# 03_-_28Pins_Schematic.net
KiCad netlist of a schematic drawn in Altium Designer
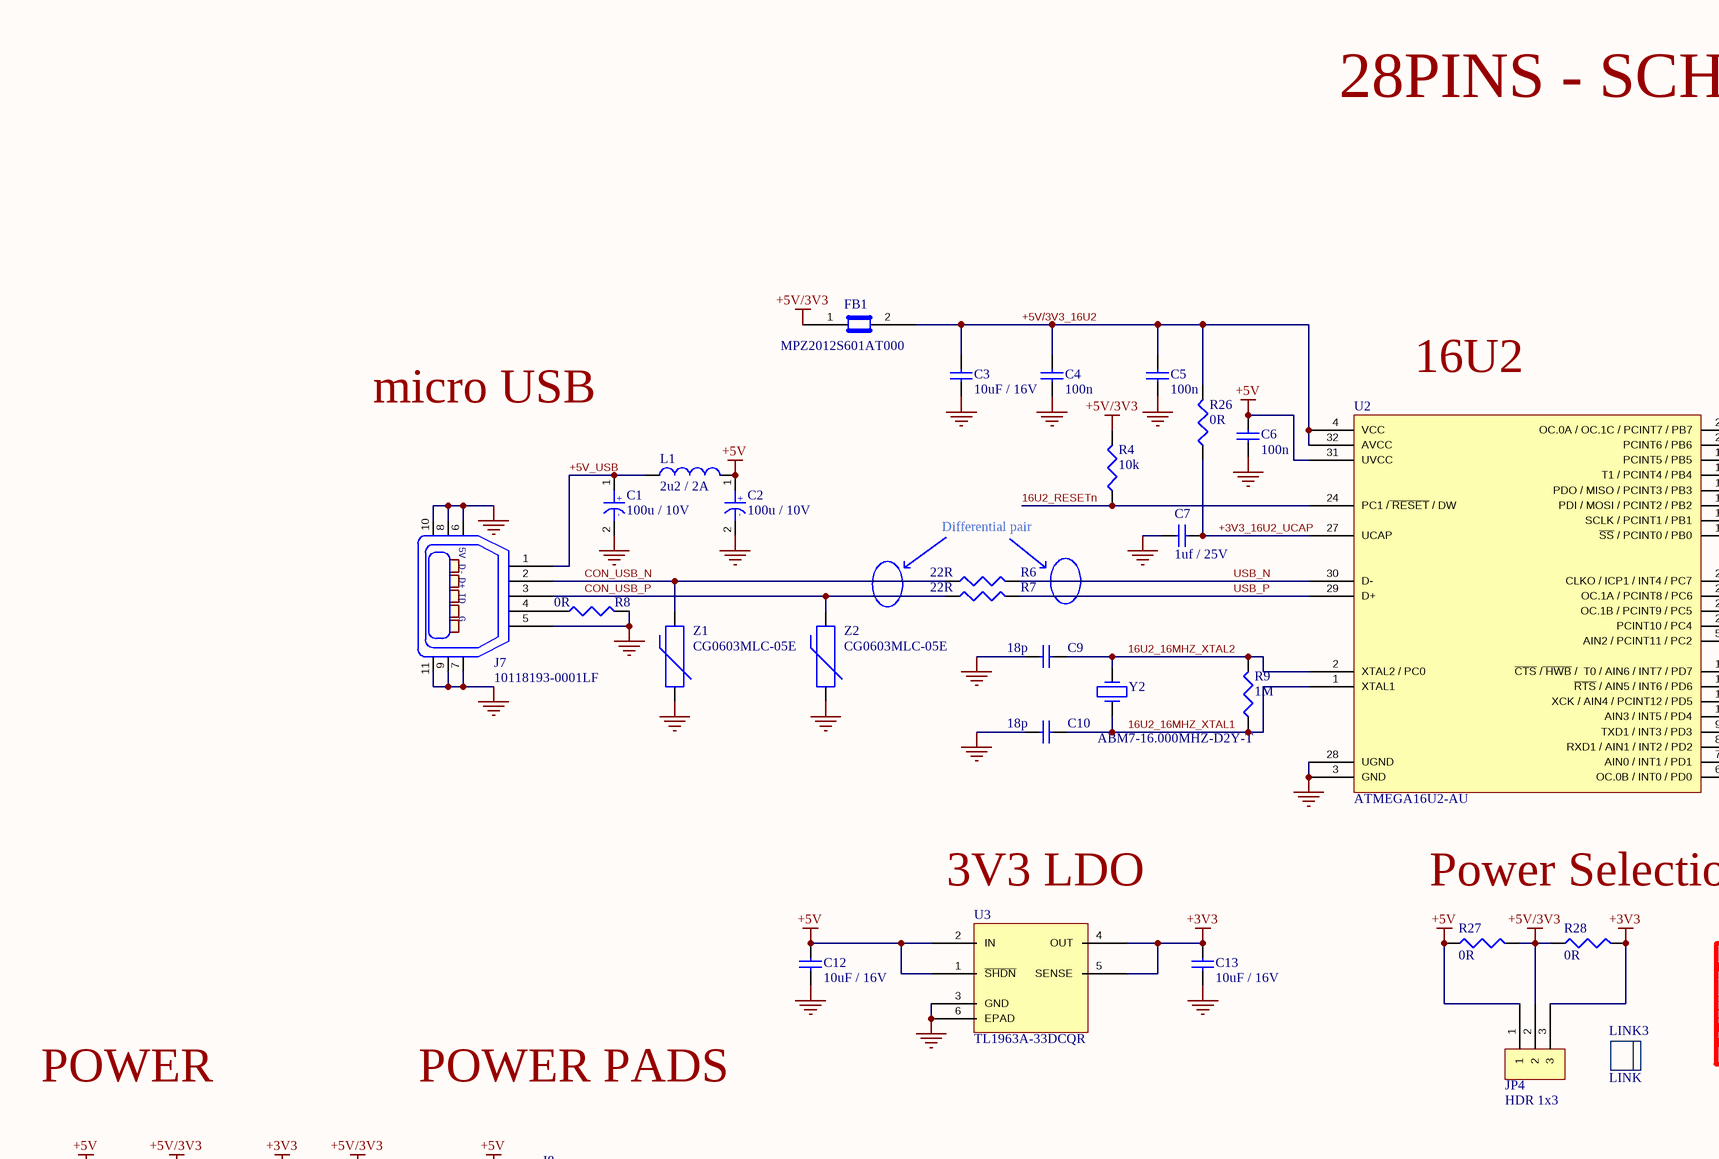
[diagram p0: [03] - 28Pins_Schematic.SchDoc, top left]
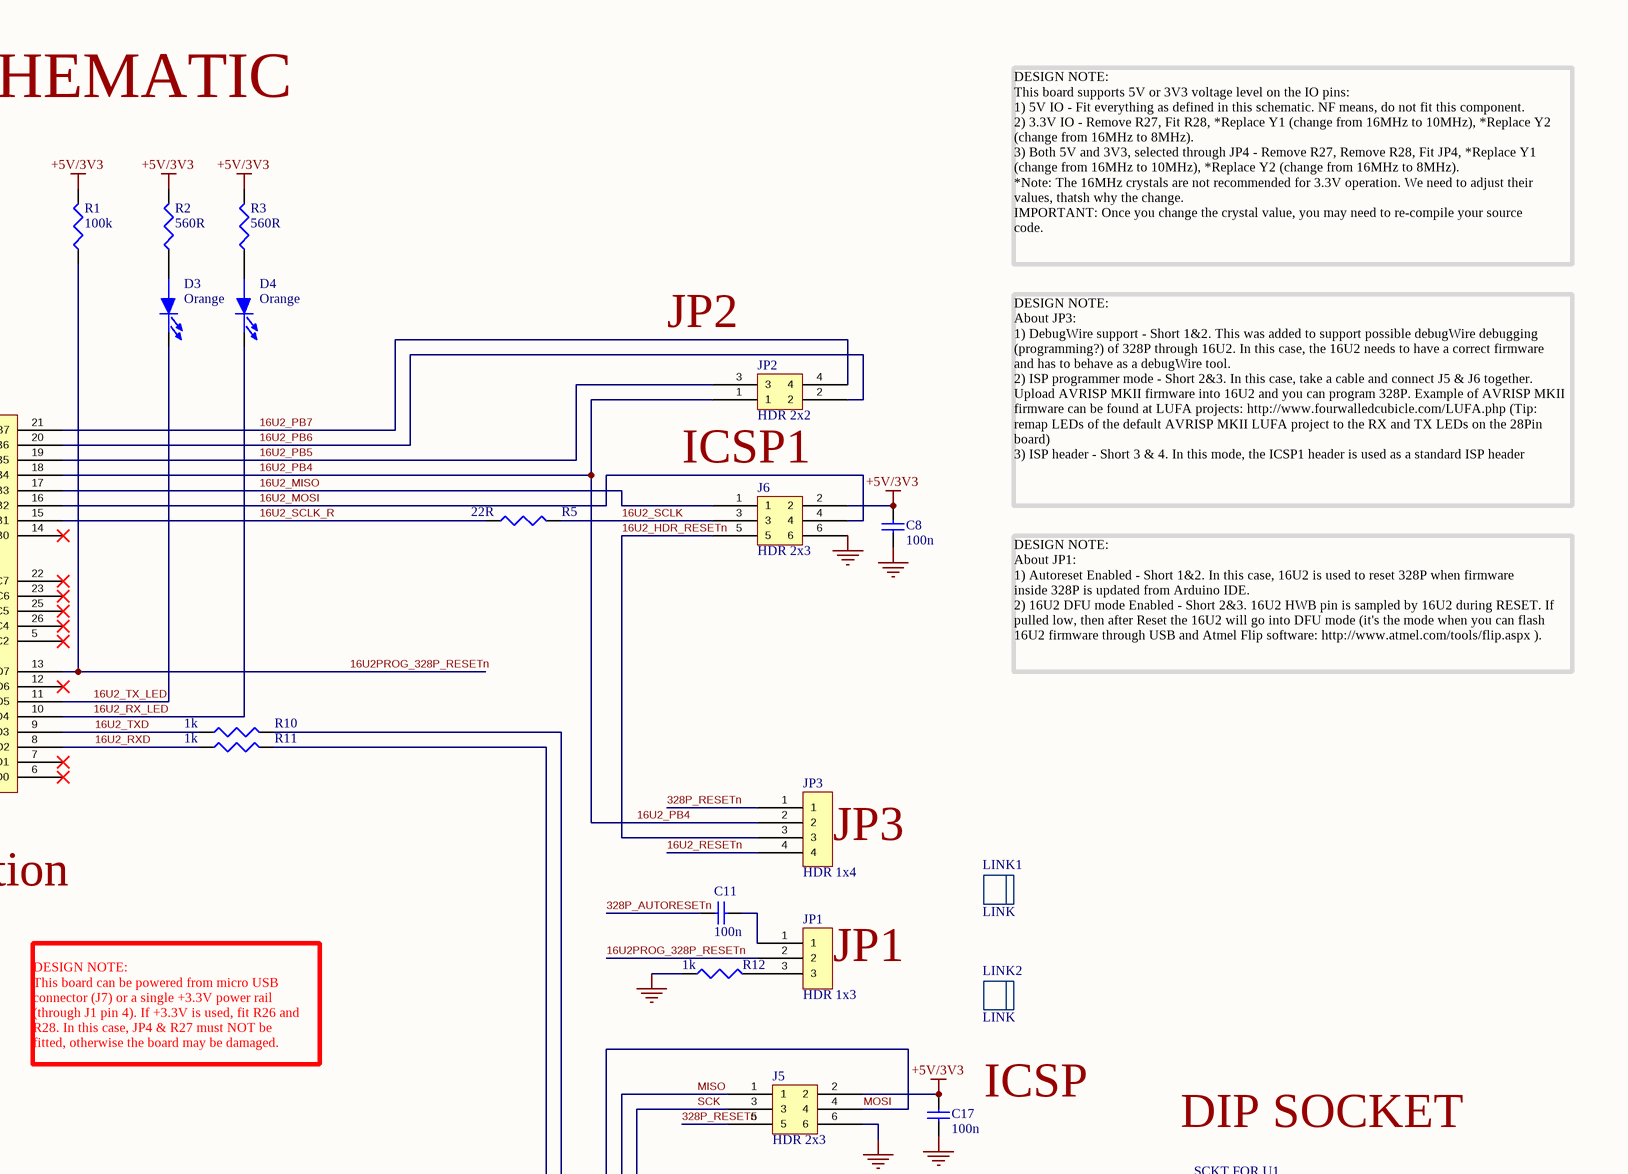
[diagram p1: [03] - 28Pins_Schematic.SchDoc, top right]
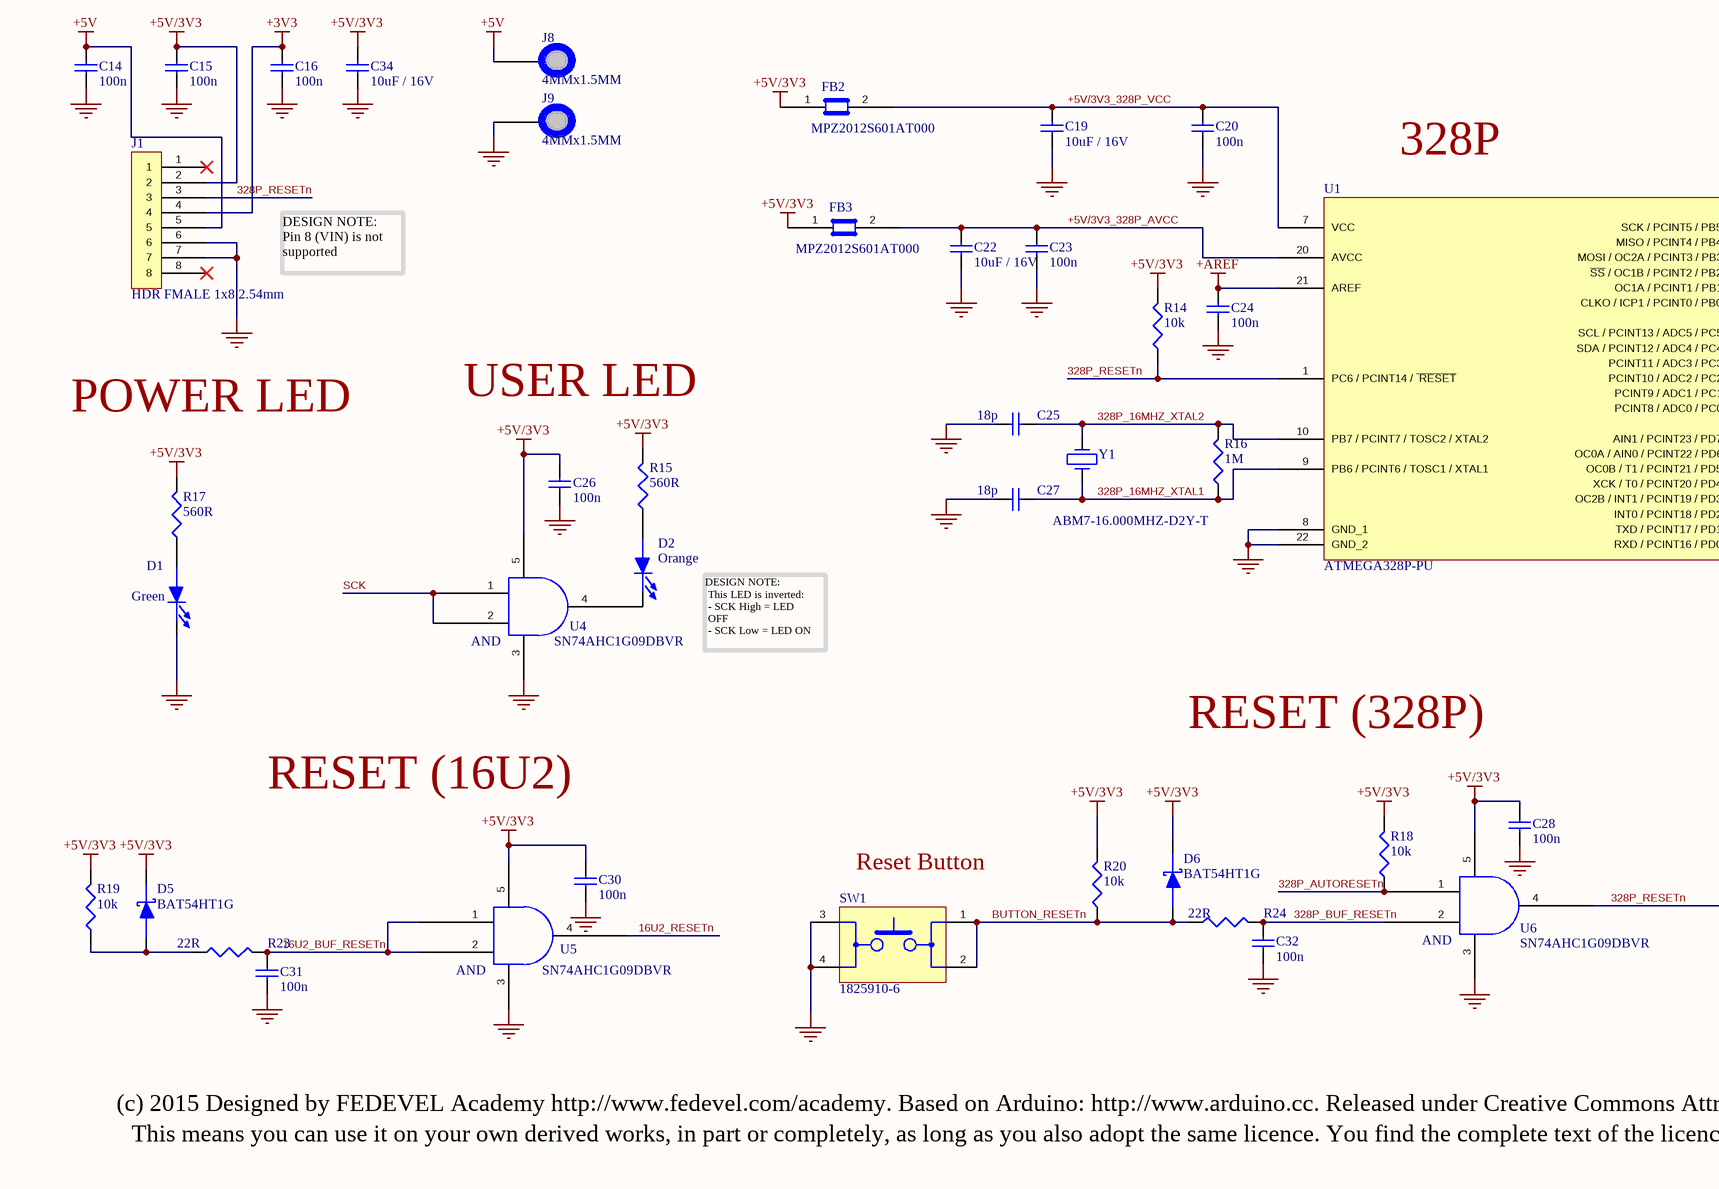
[diagram p2: [03] - 28Pins_Schematic.SchDoc, bottom left]
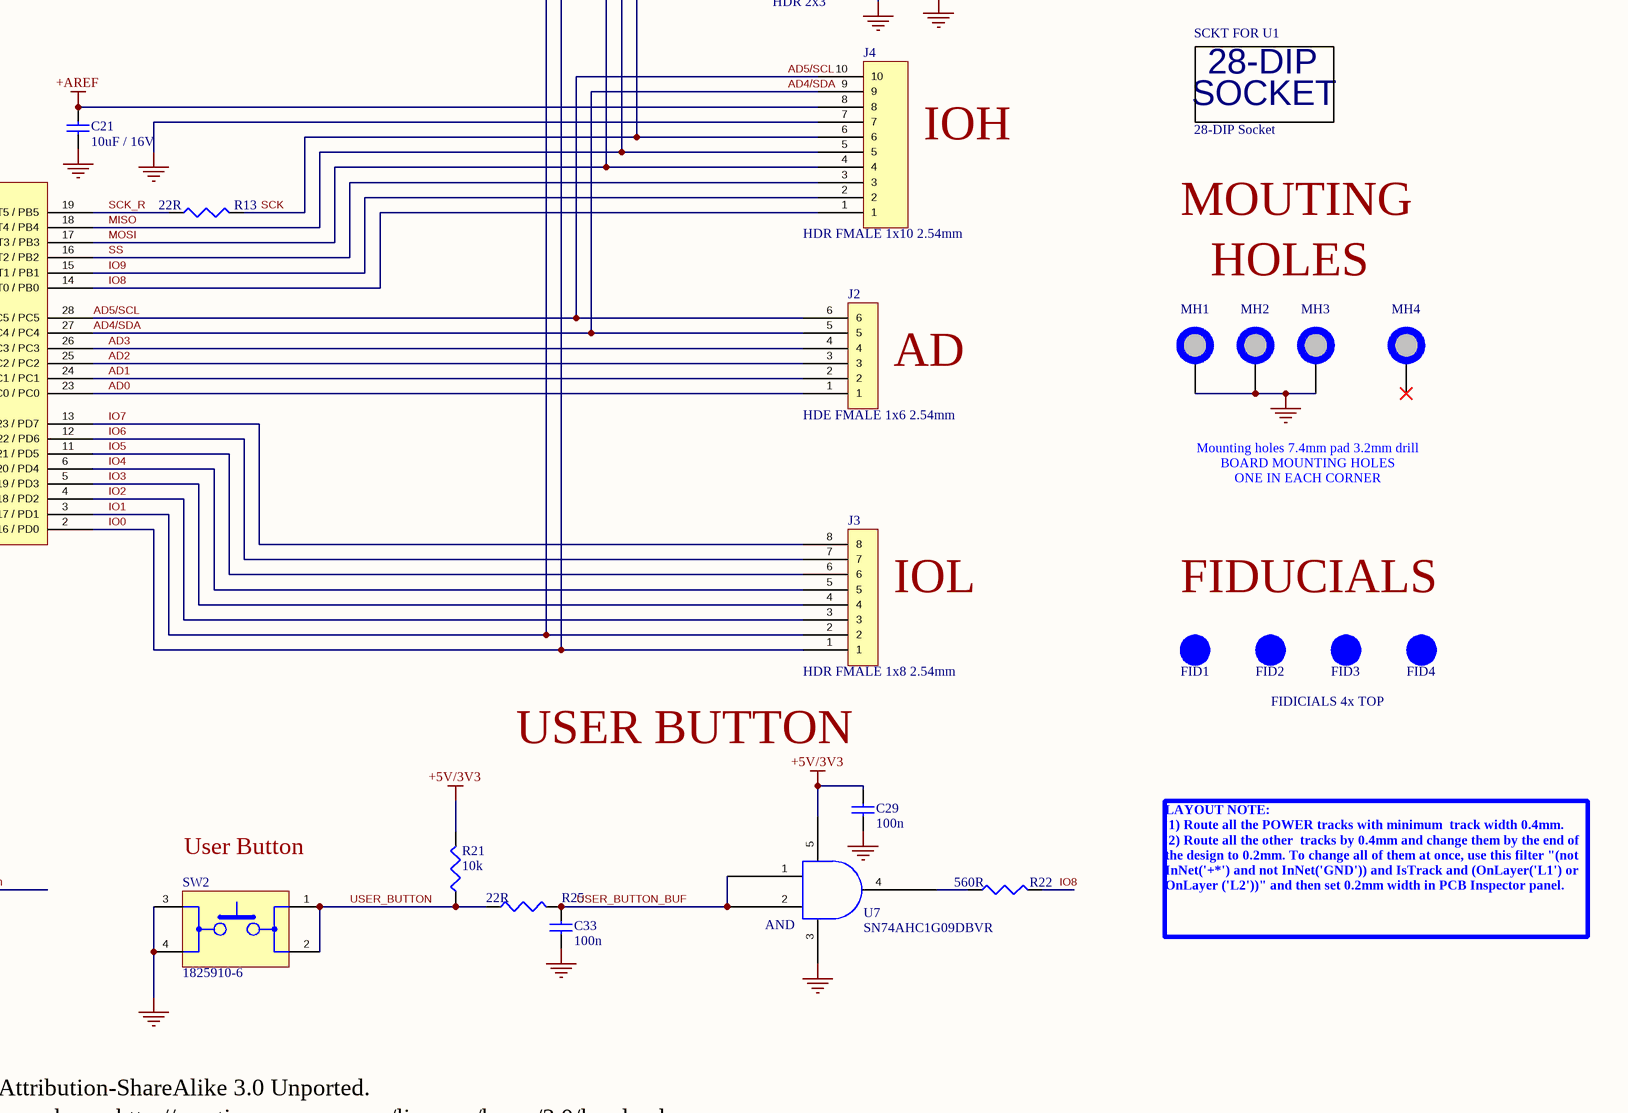
[diagram p3: [03] - 28Pins_Schematic.SchDoc, bottom right]

(export (version "E")
  (design (tool "Eeschema 10.0.6"))
  (components
    (comp (ref "C1")
      (value "100u / 10V")
      (footprint "C_ALU_C_SIZE")
      (description "Cap Aluminum Lytic 100uF 10V 20% (5 X 5.4mm) SMD 50mA 1000h 85C Automotive T/R")
      (fields
        (field (name "MANUFACTURER") "Panasonic")
        (field (name "MANUFACTURER PART NUMBER") "EEE-1AA101WR")
      )
      (libsource (lib "28Pins_Project_V1I1") (part "EEE-1AA101WR"))
    )
    (comp (ref "C2")
      (value "100u / 10V")
      (footprint "C_ALU_C_SIZE")
      (description "Cap Aluminum Lytic 100uF 10V 20% (5 X 5.4mm) SMD 50mA 1000h 85C Automotive T/R")
      (fields
        (field (name "MANUFACTURER") "Panasonic")
        (field (name "MANUFACTURER PART NUMBER") "EEE-1AA101WR")
      )
      (libsource (lib "28Pins_Project_V1I1") (part "EEE-1AA101WR"))
    )
    (comp (ref "C3")
      (value "10uF / 16V")
      (footprint "C0805 - 10uf")
      (description "CAP CER 10UF 16V X5R 0805")
      (fields
        (field (name "MANUFACTURER") "TDK")
        (field (name "MANUFACTURER PART NUMBER") "C2012X5R1C106M125AC")
      )
      (libsource (lib "28Pins_Project_V1I1") (part "C2012X5R1C106M125AC"))
    )
    (comp (ref "C4")
      (value "100n")
      (footprint "C0805")
      (description "CAP CER 0.1UF 50V X7R 0805")
      (fields
        (field (name "MANUFACTURER") "TDK")
        (field (name "MANUFACTURER PART NUMBER") "C2012X7R1H104K085AA")
      )
      (libsource (lib "28Pins_Project_V1I1") (part "C2012X7R1H104K085AA"))
    )
    (comp (ref "C5")
      (value "100n")
      (footprint "C0805")
      (description "CAP CER 0.1UF 50V X7R 0805")
      (fields
        (field (name "MANUFACTURER") "TDK")
        (field (name "MANUFACTURER PART NUMBER") "C2012X7R1H104K085AA")
      )
      (libsource (lib "28Pins_Project_V1I1") (part "C2012X7R1H104K085AA"))
    )
    (comp (ref "C6")
      (value "100n")
      (footprint "C0805")
      (description "CAP CER 0.1UF 50V X7R 0805")
      (fields
        (field (name "MANUFACTURER") "TDK")
        (field (name "MANUFACTURER PART NUMBER") "C2012X7R1H104K085AA")
      )
      (libsource (lib "28Pins_Project_V1I1") (part "C2012X7R1H104K085AA"))
    )
    (comp (ref "C7")
      (value "1uf / 25V")
      (footprint "C0805")
      (description "CAP CER 1UF 25V X5R 0805")
      (fields
        (field (name "MANUFACTURER") "TDK")
        (field (name "MANUFACTURER PART NUMBER") "C2012X5R1E105K125AA")
      )
      (libsource (lib "28Pins_Project_V1I1") (part "C2012X5R1E105K125AA"))
    )
    (comp (ref "C8")
      (value "100n")
      (footprint "C0805")
      (description "CAP CER 0.1UF 50V X7R 0805")
      (fields
        (field (name "MANUFACTURER") "TDK")
        (field (name "MANUFACTURER PART NUMBER") "C2012X7R1H104K085AA")
      )
      (libsource (lib "28Pins_Project_V1I1") (part "C2012X7R1H104K085AA"))
    )
    (comp (ref "C9")
      (value "18p")
      (footprint "C0805")
      (description "CAP CER 18PF 50V NP0 0805")
      (fields
        (field (name "MANUFACTURER") "KEMET")
        (field (name "MANUFACTURER PART NUMBER") "C0805C180J5GAC-TU")
      )
      (libsource (lib "28Pins_Project_V1I1") (part "C0805C180J5GAC-TU"))
    )
    (comp (ref "C10")
      (value "18p")
      (footprint "C0805")
      (description "CAP CER 18PF 50V NP0 0805")
      (fields
        (field (name "MANUFACTURER") "KEMET")
        (field (name "MANUFACTURER PART NUMBER") "C0805C180J5GAC-TU")
      )
      (libsource (lib "28Pins_Project_V1I1") (part "C0805C180J5GAC-TU"))
    )
    (comp (ref "C11")
      (value "100n")
      (footprint "C0805")
      (description "CAP CER 0.1UF 50V X7R 0805")
      (fields
        (field (name "MANUFACTURER") "TDK")
        (field (name "MANUFACTURER PART NUMBER") "C2012X7R1H104K085AA")
      )
      (libsource (lib "28Pins_Project_V1I1") (part "C2012X7R1H104K085AA"))
    )
    (comp (ref "C12")
      (value "10uF / 16V")
      (footprint "C0805 - 10uf")
      (description "CAP CER 10UF 16V X5R 0805")
      (fields
        (field (name "MANUFACTURER") "TDK")
        (field (name "MANUFACTURER PART NUMBER") "C2012X5R1C106M125AC")
      )
      (libsource (lib "28Pins_Project_V1I1") (part "C2012X5R1C106M125AC"))
    )
    (comp (ref "C13")
      (value "10uF / 16V")
      (footprint "C0805 - 10uf")
      (description "CAP CER 10UF 16V X5R 0805")
      (fields
        (field (name "MANUFACTURER") "TDK")
        (field (name "MANUFACTURER PART NUMBER") "C2012X5R1C106M125AC")
      )
      (libsource (lib "28Pins_Project_V1I1") (part "C2012X5R1C106M125AC"))
    )
    (comp (ref "C14")
      (value "100n")
      (footprint "C0805")
      (description "CAP CER 0.1UF 50V X7R 0805")
      (fields
        (field (name "MANUFACTURER") "TDK")
        (field (name "MANUFACTURER PART NUMBER") "C2012X7R1H104K085AA")
      )
      (libsource (lib "28Pins_Project_V1I1") (part "C2012X7R1H104K085AA"))
    )
    (comp (ref "C15")
      (value "100n")
      (footprint "C0805")
      (description "CAP CER 0.1UF 50V X7R 0805")
      (fields
        (field (name "MANUFACTURER") "TDK")
        (field (name "MANUFACTURER PART NUMBER") "C2012X7R1H104K085AA")
      )
      (libsource (lib "28Pins_Project_V1I1") (part "C2012X7R1H104K085AA"))
    )
    (comp (ref "C16")
      (value "100n")
      (footprint "C0805")
      (description "CAP CER 0.1UF 50V X7R 0805")
      (fields
        (field (name "MANUFACTURER") "TDK")
        (field (name "MANUFACTURER PART NUMBER") "C2012X7R1H104K085AA")
      )
      (libsource (lib "28Pins_Project_V1I1") (part "C2012X7R1H104K085AA"))
    )
    (comp (ref "C17")
      (value "100n")
      (footprint "C0805")
      (description "CAP CER 0.1UF 50V X7R 0805")
      (fields
        (field (name "MANUFACTURER") "TDK")
        (field (name "MANUFACTURER PART NUMBER") "C2012X7R1H104K085AA")
      )
      (libsource (lib "28Pins_Project_V1I1") (part "C2012X7R1H104K085AA"))
    )
    (comp (ref "C19")
      (value "10uF / 16V")
      (footprint "C0805 - 10uf")
      (description "CAP CER 10UF 16V X5R 0805")
      (fields
        (field (name "MANUFACTURER") "TDK")
        (field (name "MANUFACTURER PART NUMBER") "C2012X5R1C106M125AC")
      )
      (libsource (lib "28Pins_Project_V1I1") (part "C2012X5R1C106M125AC"))
    )
    (comp (ref "C20")
      (value "100n")
      (footprint "C0805")
      (description "CAP CER 0.1UF 50V X7R 0805")
      (fields
        (field (name "MANUFACTURER") "TDK")
        (field (name "MANUFACTURER PART NUMBER") "C2012X7R1H104K085AA")
      )
      (libsource (lib "28Pins_Project_V1I1") (part "C2012X7R1H104K085AA"))
    )
    (comp (ref "C21")
      (value "10uF / 16V")
      (footprint "C0805 - 10uf")
      (description "CAP CER 10UF 16V X5R 0805")
      (fields
        (field (name "MANUFACTURER") "TDK")
        (field (name "MANUFACTURER PART NUMBER") "C2012X5R1C106M125AC")
      )
      (libsource (lib "28Pins_Project_V1I1") (part "C2012X5R1C106M125AC"))
    )
    (comp (ref "C22")
      (value "10uF / 16V")
      (footprint "C0805 - 10uf")
      (description "CAP CER 10UF 16V X5R 0805")
      (fields
        (field (name "MANUFACTURER") "TDK")
        (field (name "MANUFACTURER PART NUMBER") "C2012X5R1C106M125AC")
      )
      (libsource (lib "28Pins_Project_V1I1") (part "C2012X5R1C106M125AC"))
    )
    (comp (ref "C23")
      (value "100n")
      (footprint "C0805")
      (description "CAP CER 0.1UF 50V X7R 0805")
      (fields
        (field (name "MANUFACTURER") "TDK")
        (field (name "MANUFACTURER PART NUMBER") "C2012X7R1H104K085AA")
      )
      (libsource (lib "28Pins_Project_V1I1") (part "C2012X7R1H104K085AA"))
    )
    (comp (ref "C24")
      (value "100n")
      (footprint "C0805")
      (description "CAP CER 0.1UF 50V X7R 0805")
      (fields
        (field (name "MANUFACTURER") "TDK")
        (field (name "MANUFACTURER PART NUMBER") "C2012X7R1H104K085AA")
      )
      (libsource (lib "28Pins_Project_V1I1") (part "C2012X7R1H104K085AA"))
    )
    (comp (ref "C25")
      (value "18p")
      (footprint "C0805")
      (description "CAP CER 18PF 50V NP0 0805")
      (fields
        (field (name "MANUFACTURER") "KEMET")
        (field (name "MANUFACTURER PART NUMBER") "C0805C180J5GAC-TU")
      )
      (libsource (lib "28Pins_Project_V1I1") (part "C0805C180J5GAC-TU"))
    )
    (comp (ref "C26")
      (value "100n")
      (footprint "C0805")
      (description "CAP CER 0.1UF 50V X7R 0805")
      (fields
        (field (name "MANUFACTURER") "TDK")
        (field (name "MANUFACTURER PART NUMBER") "C2012X7R1H104K085AA")
      )
      (libsource (lib "28Pins_Project_V1I1") (part "C2012X7R1H104K085AA"))
    )
    (comp (ref "C27")
      (value "18p")
      (footprint "C0805")
      (description "CAP CER 18PF 50V NP0 0805")
      (fields
        (field (name "MANUFACTURER") "KEMET")
        (field (name "MANUFACTURER PART NUMBER") "C0805C180J5GAC-TU")
      )
      (libsource (lib "28Pins_Project_V1I1") (part "C0805C180J5GAC-TU"))
    )
    (comp (ref "C28")
      (value "100n")
      (footprint "C0805")
      (description "CAP CER 0.1UF 50V X7R 0805")
      (fields
        (field (name "MANUFACTURER") "TDK")
        (field (name "MANUFACTURER PART NUMBER") "C2012X7R1H104K085AA")
      )
      (libsource (lib "28Pins_Project_V1I1") (part "C2012X7R1H104K085AA"))
    )
    (comp (ref "C29")
      (value "100n")
      (footprint "C0805")
      (description "CAP CER 0.1UF 50V X7R 0805")
      (fields
        (field (name "MANUFACTURER") "TDK")
        (field (name "MANUFACTURER PART NUMBER") "C2012X7R1H104K085AA")
      )
      (libsource (lib "28Pins_Project_V1I1") (part "C2012X7R1H104K085AA"))
    )
    (comp (ref "C30")
      (value "100n")
      (footprint "C0805")
      (description "CAP CER 0.1UF 50V X7R 0805")
      (fields
        (field (name "MANUFACTURER") "TDK")
        (field (name "MANUFACTURER PART NUMBER") "C2012X7R1H104K085AA")
      )
      (libsource (lib "28Pins_Project_V1I1") (part "C2012X7R1H104K085AA"))
    )
    (comp (ref "C31")
      (value "100n")
      (footprint "C0805")
      (description "CAP CER 0.1UF 50V X7R 0805")
      (fields
        (field (name "MANUFACTURER") "TDK")
        (field (name "MANUFACTURER PART NUMBER") "C2012X7R1H104K085AA")
      )
      (libsource (lib "28Pins_Project_V1I1") (part "C2012X7R1H104K085AA"))
    )
    (comp (ref "C32")
      (value "100n")
      (footprint "C0805")
      (description "CAP CER 0.1UF 50V X7R 0805")
      (fields
        (field (name "MANUFACTURER") "TDK")
        (field (name "MANUFACTURER PART NUMBER") "C2012X7R1H104K085AA")
      )
      (libsource (lib "28Pins_Project_V1I1") (part "C2012X7R1H104K085AA"))
    )
    (comp (ref "C33")
      (value "100n")
      (footprint "C0805")
      (description "CAP CER 0.1UF 50V X7R 0805")
      (fields
        (field (name "MANUFACTURER") "TDK")
        (field (name "MANUFACTURER PART NUMBER") "C2012X7R1H104K085AA")
      )
      (libsource (lib "28Pins_Project_V1I1") (part "C2012X7R1H104K085AA"))
    )
    (comp (ref "C34")
      (value "10uF / 16V")
      (footprint "C0805 - 10uf")
      (description "CAP CER 10UF 16V X5R 0805")
      (fields
        (field (name "MANUFACTURER") "TDK")
        (field (name "MANUFACTURER PART NUMBER") "C2012X5R1C106M125AC")
      )
      (libsource (lib "28Pins_Project_V1I1") (part "C2012X5R1C106M125AC"))
    )
    (comp (ref "D1")
      (value "Green")
      (footprint "LED_0603")
      (description "LED GREEN DIFFUSED 0603 SMD")
      (fields
        (field (name "MANUFACTURER") "Osram Opto")
        (field (name "MANUFACTURER PART NUMBER") "LGL29K-G2J1-24-Z")
      )
      (libsource (lib "28Pins_Project_V1I1") (part "LGL29K-G2J1-24-Z"))
    )
    (comp (ref "D2")
      (value "Orange")
      (footprint "LED_0603")
      (description "LED ORANGE DIFFUSED 0603 SMD")
      (fields
        (field (name "MANUFACTURER") "Osram Opto")
        (field (name "MANUFACTURER PART NUMBER") "LOL29K-H2K1-24-Z")
      )
      (libsource (lib "28Pins_Project_V1I1") (part "LOL29K-H2K1-24-Z"))
    )
    (comp (ref "D3")
      (value "Orange")
      (footprint "LED_0603")
      (description "LED ORANGE DIFFUSED 0603 SMD")
      (fields
        (field (name "MANUFACTURER") "Osram Opto")
        (field (name "MANUFACTURER PART NUMBER") "LOL29K-H2K1-24-Z")
      )
      (libsource (lib "28Pins_Project_V1I1") (part "LOL29K-H2K1-24-Z"))
    )
    (comp (ref "D4")
      (value "Orange")
      (footprint "LED_0603")
      (description "LED ORANGE DIFFUSED 0603 SMD")
      (fields
        (field (name "MANUFACTURER") "Osram Opto")
        (field (name "MANUFACTURER PART NUMBER") "LOL29K-H2K1-24-Z")
      )
      (libsource (lib "28Pins_Project_V1I1") (part "LOL29K-H2K1-24-Z"))
    )
    (comp (ref "D5")
      (value "BAT54HT1G")
      (footprint "SOD323")
      (description "DIODE SCHOTTKY 30V 200MA SOD323")
      (fields (field (name "MANUFACTURER") "ON Semiconductor / Fairchild"))
      (libsource (lib "28Pins_Project_V1I1") (part "BAT54HT1G"))
    )
    (comp (ref "D6")
      (value "BAT54HT1G")
      (footprint "SOD323")
      (description "DIODE SCHOTTKY 30V 200MA SOD323")
      (fields (field (name "MANUFACTURER") "ON Semiconductor / Fairchild"))
      (libsource (lib "28Pins_Project_V1I1") (part "BAT54HT1G"))
    )
    (comp (ref "FB1")
      (value "MPZ2012S601AT000")
      (footprint "C0805")
      (description "TDK   MPZ2012S601AT000   FERRITE BEAD, 0.1OHM, 2A, 0805, FULL REEL")
      (fields (field (name "MANUFACTURER") "TDK"))
      (libsource (lib "28Pins_Project_V1I1") (part "MPZ2012S601AT000"))
    )
    (comp (ref "FB2")
      (value "MPZ2012S601AT000")
      (footprint "C0805")
      (description "TDK   MPZ2012S601AT000   FERRITE BEAD, 0.1OHM, 2A, 0805, FULL REEL")
      (fields (field (name "MANUFACTURER") "TDK"))
      (libsource (lib "28Pins_Project_V1I1") (part "MPZ2012S601AT000"))
    )
    (comp (ref "FB3")
      (value "MPZ2012S601AT000")
      (footprint "C0805")
      (description "TDK   MPZ2012S601AT000   FERRITE BEAD, 0.1OHM, 2A, 0805, FULL REEL")
      (fields (field (name "MANUFACTURER") "TDK"))
      (libsource (lib "28Pins_Project_V1I1") (part "MPZ2012S601AT000"))
    )
    (comp (ref "FID1")
      (value "FID_1MMC")
      (footprint "FID_40x120D")
      (description "Fiducial 40mil Diameter, 20mil Mask")
      (libsource (lib "28Pins_Project_V1I1") (part "FID_1MMC"))
    )
    (comp (ref "FID2")
      (value "FID_1MMC")
      (footprint "FID_40x120D")
      (description "Fiducial 40mil Diameter, 20mil Mask")
      (libsource (lib "28Pins_Project_V1I1") (part "FID_1MMC"))
    )
    (comp (ref "FID3")
      (value "FID_1MMC")
      (footprint "FID_40x120D")
      (description "Fiducial 40mil Diameter, 20mil Mask")
      (libsource (lib "28Pins_Project_V1I1") (part "FID_1MMC"))
    )
    (comp (ref "FID4")
      (value "FID_1MMC")
      (footprint "FID_40x120D")
      (description "Fiducial 40mil Diameter, 20mil Mask")
      (libsource (lib "28Pins_Project_V1I1") (part "FID_1MMC"))
    )
    (comp (ref "J1")
      (value "HDR FMALE 1x8 2.54mm")
      (footprint "HDR FMALE 1x8 2.54mm")
      (description "Headers & Wire Housings 8 PIN SIL VERTICAL SOCKET GOLD+TIN")
      (fields (field (name "MANUFACTURER") "Harwin") (field (name "MANUFACTURER PART NUMBER") "M20-7820842"))
      (libsource (lib "28Pins_Project_V1I1") (part "M20-7820842"))
    )
    (comp (ref "J2")
      (value "HDE FMALE 1x6 2.54mm")
      (footprint "HDR FMALE 1x6 2.54mm")
      (description "Headers & Wire Housings 6 PIN SIL VERTICAL SOCKET TIN")
      (fields (field (name "MANUFACTURER") "Harwin") (field (name "MANUFACTURER PART NUMBER") "M20-7820646"))
      (libsource (lib "28Pins_Project_V1I1") (part "M20-7820646"))
    )
    (comp (ref "J3")
      (value "HDR FMALE 1x8 2.54mm")
      (footprint "HDR FMALE 1x8 2.54mm")
      (description "Headers & Wire Housings 8 PIN SIL VERTICAL SOCKET GOLD+TIN")
      (fields (field (name "MANUFACTURER") "Harwin") (field (name "MANUFACTURER PART NUMBER") "M20-7820842"))
      (libsource (lib "") (part "M20-7820842_1"))
    )
    (comp (ref "J4")
      (value "HDR FMALE 1x10 2.54mm")
      (footprint "HDR FMALE 1x10 2.54mm")
      (description "Headers & Wire Housings 10 PIN SIL VERTICAL SOCKET TIN")
      (fields (field (name "MANUFACTURER") "Harwin") (field (name "MANUFACTURER PART NUMBER") "M20-7821046"))
      (libsource (lib "28Pins_Project_V1I1") (part "M20-7821046"))
    )
    (comp (ref "J5")
      (value "HDR 2x3")
      (footprint "HDR_2x3_2.54mm")
      (description "6 Positions Header, Unshrouded Connector 0.100\" (2.54mm) Through Hole Gold or Gold, GXT™")
      (fields
        (field (name "MANUFACTURER") "Amphenol FCI")
        (field (name "MANUFACTURER PART NUMBER") "67997-106HLF")
      )
      (libsource (lib "28Pins_Project_V1I1") (part "67997-106HLF"))
    )
    (comp (ref "J6")
      (value "HDR 2x3")
      (footprint "HDR_2x3_2.54mm")
      (description "6 Positions Header, Unshrouded Connector 0.100\" (2.54mm) Through Hole Gold or Gold, GXT™")
      (fields
        (field (name "MANUFACTURER") "Amphenol FCI")
        (field (name "MANUFACTURER PART NUMBER") "67997-106HLF")
      )
      (libsource (lib "28Pins_Project_V1I1") (part "67997-106HLF"))
    )
    (comp (ref "J7")
      (value "10118193-0001LF")
      (footprint "10118193")
      (description "USB - micro B USB 2.0 Receptacle Connector 5 Position Surface Mount, Right Angle, Horizontal")
      (fields (field (name "MANUFACTURER") "Amphenol FCI"))
      (libsource (lib "28Pins_Project_V1I1") (part "10118193-0001LF"))
    )
    (comp (ref "J8")
      (value "4MMx1.5MM")
      (footprint "PAD_WITH_HOLE_4MMx1.5MM")
      (description "Pad with a hole 4mmx1.5mm")
      (libsource (lib "28Pins_Project_V1I1") (part "PAD_WITH_HOLE_4MMx1.5MM"))
    )
    (comp (ref "J9")
      (value "4MMx1.5MM")
      (footprint "PAD_WITH_HOLE_4MMx1.5MM")
      (description "Pad with a hole 4mmx1.5mm")
      (libsource (lib "28Pins_Project_V1I1") (part "PAD_WITH_HOLE_4MMx1.5MM"))
    )
    (comp (ref "JP1")
      (value "HDR 1x3")
      (footprint "HDR FMALE 1x3 2.54mm")
      (description "3 Positions Header, Unshrouded Connector 0.100\" (2.54mm) Through Hole Gold or Gold, GXT™")
      (fields
        (field (name "MANUFACTURER") "Amphenol FCI")
        (field (name "MANUFACTURER PART NUMBER") "68000-103HLF")
      )
      (libsource (lib "") (part "68000-103HLF_1"))
    )
    (comp (ref "JP2")
      (value "HDR 2x2")
      (footprint "HDR_2x2_2.54mm")
      (description "4 Positions Header, Unshrouded Connector 0.100\" (2.54mm) Through Hole Gold or Gold, GXT™")
      (fields
        (field (name "MANUFACTURER") "Amphenol FCI")
        (field (name "MANUFACTURER PART NUMBER") "68602-204HLF")
      )
      (libsource (lib "28Pins_Project_V1I1") (part "68602-204HLF"))
    )
    (comp (ref "JP3")
      (value "HDR 1x4")
      (footprint "HDR _1x4_2.54mm")
      (description "4 Positions Header, Unshrouded Connector 0.100\" (2.54mm) Through Hole Gold or Gold, GXT™")
      (fields
        (field (name "MANUFACTURER") "Amphenol FCI")
        (field (name "MANUFACTURER PART NUMBER") "68001-204HLF")
      )
      (libsource (lib "28Pins_Project_V1I1") (part "68001-204HLF"))
    )
    (comp (ref "JP4")
      (value "HDR 1x3")
      (footprint "HDR FMALE 1x3 2.54mm")
      (description "3 Positions Header, Unshrouded Connector 0.100\" (2.54mm) Through Hole Gold or Gold, GXT™")
      (fields
        (field (name "MANUFACTURER") "Amphenol FCI")
        (field (name "MANUFACTURER PART NUMBER") "68000-103HLF")
      )
      (libsource (lib "28Pins_Project_V1I1") (part "68000-103HLF"))
    )
    (comp (ref "L1")
      (value "2u2 / 2A")
      (footprint "C1210_IND")
      (description "Inductor Chip Wirewound 2.2uH 20% 100KHz 1.13A 80mOhm DCR 1210 T/R")
      (fields
        (field (name "MANUFACTURER") "KEMET")
        (field (name "MANUFACTURER PART NUMBER") "L1210R2R2MDWIT")
      )
      (libsource (lib "28Pins_Project_V1I1") (part "L1210R2R2MDWIT"))
    )
    (comp (ref "LINK1")
      (value "LINK")
      (description "CONN JUMPER SHORTING .100\" GOLD")
      (fields
        (field (name "MANUFACTURER") "Sullins")
        (field (name "MANUFACTURER PART NUMBER") "QPC02SXGN-RC")
      )
      (libsource (lib "28Pins_Project_V1I1") (part "QPC02SXGN-RC"))
    )
    (comp (ref "LINK2")
      (value "LINK")
      (description "CONN JUMPER SHORTING .100\" GOLD")
      (fields
        (field (name "MANUFACTURER") "Sullins")
        (field (name "MANUFACTURER PART NUMBER") "QPC02SXGN-RC")
      )
      (libsource (lib "28Pins_Project_V1I1") (part "QPC02SXGN-RC"))
    )
    (comp (ref "LINK3")
      (value "LINK")
      (description "CONN JUMPER SHORTING .100\" GOLD")
      (fields
        (field (name "MANUFACTURER") "Sullins")
        (field (name "MANUFACTURER PART NUMBER") "QPC02SXGN-RC")
      )
      (libsource (lib "28Pins_Project_V1I1") (part "QPC02SXGN-RC"))
    )
    (comp (ref "MH1")
      (value "MH_7.4MMC_3.2MMD")
      (footprint "MH_7.4MMC_3.2MMD")
      (description "Mounting Hole 7.4mm Diameter, 3.2mm Drill")
      (libsource (lib "28Pins_Project_V1I1") (part "MH_7.4MMC_3.2MMD"))
    )
    (comp (ref "MH2")
      (value "MH_7.4MMC_3.2MMD")
      (footprint "MH_7.4MMC_3.2MMD")
      (description "Mounting Hole 7.4mm Diameter, 3.2mm Drill")
      (libsource (lib "28Pins_Project_V1I1") (part "MH_7.4MMC_3.2MMD"))
    )
    (comp (ref "MH3")
      (value "MH_7.4MMC_3.2MMD")
      (footprint "MH_7.4MMC_3.2MMD")
      (description "Mounting Hole 7.4mm Diameter, 3.2mm Drill")
      (libsource (lib "28Pins_Project_V1I1") (part "MH_7.4MMC_3.2MMD"))
    )
    (comp (ref "MH4")
      (value "MH_7.4MMNC_3.2MMD")
      (footprint "MH_7.4MMNC_3.2MMD_NON_COPPER_NPTH")
      (description "Hole 7.4mm Diameter (Non Copper), 3.2mm Drill NPTH")
      (libsource (lib "28Pins_Project_V1I1") (part "MH_7.4MMNC_3.2MMD"))
    )
    (comp (ref "R1")
      (value "100k")
      (footprint "R0805")
      (description "RES SMD 100K OHM 1% 1/8W 0805")
      (fields
        (field (name "MANUFACTURER") "Yageo")
        (field (name "MANUFACTURER PART NUMBER") "RT0805FRE07100KL")
      )
      (libsource (lib "28Pins_Project_V1I1") (part "RT0805FRE07100KL"))
    )
    (comp (ref "R2")
      (value "560R")
      (footprint "R0805")
      (description "RES SMD 560 OHM 1% 1/8W 0805")
      (fields
        (field (name "MANUFACTURER") "Yageo")
        (field (name "MANUFACTURER PART NUMBER") "RC0805FR-07560RL")
      )
      (libsource (lib "28Pins_Project_V1I1") (part "RC0805FR-07560RL"))
    )
    (comp (ref "R3")
      (value "560R")
      (footprint "R0805")
      (description "RES SMD 560 OHM 1% 1/8W 0805")
      (fields
        (field (name "MANUFACTURER") "Yageo")
        (field (name "MANUFACTURER PART NUMBER") "RC0805FR-07560RL")
      )
      (libsource (lib "28Pins_Project_V1I1") (part "RC0805FR-07560RL"))
    )
    (comp (ref "R4")
      (value "10k")
      (footprint "R0805")
      (description "RES SMD 10K OHM 1% 1/8W 0805")
      (fields
        (field (name "MANUFACTURER") "Yageo")
        (field (name "MANUFACTURER PART NUMBER") "RC0805FR-0710KL")
      )
      (libsource (lib "28Pins_Project_V1I1") (part "RC0805FR-0710KL"))
    )
    (comp (ref "R5")
      (value "22R")
      (footprint "R0805")
      (description "RES SMD 22 OHM 1% 1/8W 0805")
      (fields
        (field (name "MANUFACTURER") "Yageo")
        (field (name "MANUFACTURER PART NUMBER") "RC0805FR-0722RL")
      )
      (libsource (lib "28Pins_Project_V1I1") (part "RC0805FR-0722RL"))
    )
    (comp (ref "R6")
      (value "22R")
      (footprint "R0805")
      (description "RES SMD 22 OHM 1% 1/8W 0805")
      (fields
        (field (name "MANUFACTURER") "Yageo")
        (field (name "MANUFACTURER PART NUMBER") "RC0805FR-0722RL")
      )
      (libsource (lib "28Pins_Project_V1I1") (part "RC0805FR-0722RL"))
    )
    (comp (ref "R7")
      (value "22R")
      (footprint "R0805")
      (description "RES SMD 22 OHM 1% 1/8W 0805")
      (fields
        (field (name "MANUFACTURER") "Yageo")
        (field (name "MANUFACTURER PART NUMBER") "RC0805FR-0722RL")
      )
      (libsource (lib "28Pins_Project_V1I1") (part "RC0805FR-0722RL"))
    )
    (comp (ref "R8")
      (value "0R")
      (footprint "R0805")
      (description "YAGEO         RC0805JR-070RL             RES, THICK FILM, 0R, 0.125W, 0805")
      (fields
        (field (name "MANUFACTURER") "Yageo")
        (field (name "MANUFACTURER PART NUMBER") "RC0805JR-070RL")
      )
      (libsource (lib "28Pins_Project_V1I1") (part "RC0805JR-070RL"))
    )
    (comp (ref "R9")
      (value "1M")
      (footprint "R0805")
      (description "Yageo RC0805 Series Thick Film Surface Mount Resistor 0805 Case 1MO ±1% 0.125W ±100ppm/°C")
      (fields
        (field (name "MANUFACTURER") "Yageo Phycomp")
        (field (name "MANUFACTURER PART NUMBER") "RC0805FR-071ML")
      )
      (libsource (lib "28Pins_Project_V1I1") (part "RC0805FR-071ML"))
    )
    (comp (ref "R10")
      (value "1k")
      (footprint "R0805")
      (description "RES SMD 1K OHM 1% 1/8W 0805")
      (fields
        (field (name "MANUFACTURER") "Yageo")
        (field (name "MANUFACTURER PART NUMBER") "RC0805FR-071KL")
      )
      (libsource (lib "28Pins_Project_V1I1") (part "RC0805FR-071KL"))
    )
    (comp (ref "R11")
      (value "1k")
      (footprint "R0805")
      (description "RES SMD 1K OHM 1% 1/8W 0805")
      (fields
        (field (name "MANUFACTURER") "Yageo")
        (field (name "MANUFACTURER PART NUMBER") "RC0805FR-071KL")
      )
      (libsource (lib "28Pins_Project_V1I1") (part "RC0805FR-071KL"))
    )
    (comp (ref "R12")
      (value "1k")
      (footprint "R0805")
      (description "RES SMD 1K OHM 1% 1/8W 0805")
      (fields
        (field (name "MANUFACTURER") "Yageo")
        (field (name "MANUFACTURER PART NUMBER") "RC0805FR-071KL")
      )
      (libsource (lib "28Pins_Project_V1I1") (part "RC0805FR-071KL"))
    )
    (comp (ref "R13")
      (value "22R")
      (footprint "R0805")
      (description "RES SMD 22 OHM 1% 1/8W 0805")
      (fields
        (field (name "MANUFACTURER") "Yageo")
        (field (name "MANUFACTURER PART NUMBER") "RC0805FR-0722RL")
      )
      (libsource (lib "28Pins_Project_V1I1") (part "RC0805FR-0722RL"))
    )
    (comp (ref "R14")
      (value "10k")
      (footprint "R0805")
      (description "RES SMD 10K OHM 1% 1/8W 0805")
      (fields
        (field (name "MANUFACTURER") "Yageo")
        (field (name "MANUFACTURER PART NUMBER") "RC0805FR-0710KL")
      )
      (libsource (lib "28Pins_Project_V1I1") (part "RC0805FR-0710KL"))
    )
    (comp (ref "R15")
      (value "560R")
      (footprint "R0805")
      (description "RES SMD 560 OHM 1% 1/8W 0805")
      (fields
        (field (name "MANUFACTURER") "Yageo")
        (field (name "MANUFACTURER PART NUMBER") "RC0805FR-07560RL")
      )
      (libsource (lib "28Pins_Project_V1I1") (part "RC0805FR-07560RL"))
    )
    (comp (ref "R16")
      (value "1M")
      (footprint "R0805")
      (description "Yageo RC0805 Series Thick Film Surface Mount Resistor 0805 Case 1MO ±1% 0.125W ±100ppm/°C")
      (fields
        (field (name "MANUFACTURER") "Yageo Phycomp")
        (field (name "MANUFACTURER PART NUMBER") "RC0805FR-071ML")
      )
      (libsource (lib "28Pins_Project_V1I1") (part "RC0805FR-071ML"))
    )
    (comp (ref "R17")
      (value "560R")
      (footprint "R0805")
      (description "RES SMD 560 OHM 1% 1/8W 0805")
      (fields
        (field (name "MANUFACTURER") "Yageo")
        (field (name "MANUFACTURER PART NUMBER") "RC0805FR-07560RL")
      )
      (libsource (lib "28Pins_Project_V1I1") (part "RC0805FR-07560RL"))
    )
    (comp (ref "R18")
      (value "10k")
      (footprint "R0805")
      (description "RES SMD 10K OHM 1% 1/8W 0805")
      (fields
        (field (name "MANUFACTURER") "Yageo")
        (field (name "MANUFACTURER PART NUMBER") "RC0805FR-0710KL")
      )
      (libsource (lib "28Pins_Project_V1I1") (part "RC0805FR-0710KL"))
    )
    (comp (ref "R19")
      (value "10k")
      (footprint "R0805")
      (description "RES SMD 10K OHM 1% 1/8W 0805")
      (fields
        (field (name "MANUFACTURER") "Yageo")
        (field (name "MANUFACTURER PART NUMBER") "RC0805FR-0710KL")
      )
      (libsource (lib "28Pins_Project_V1I1") (part "RC0805FR-0710KL"))
    )
    (comp (ref "R20")
      (value "10k")
      (footprint "R0805")
      (description "RES SMD 10K OHM 1% 1/8W 0805")
      (fields
        (field (name "MANUFACTURER") "Yageo")
        (field (name "MANUFACTURER PART NUMBER") "RC0805FR-0710KL")
      )
      (libsource (lib "28Pins_Project_V1I1") (part "RC0805FR-0710KL"))
    )
    (comp (ref "R21")
      (value "10k")
      (footprint "R0805")
      (description "RES SMD 10K OHM 1% 1/8W 0805")
      (fields
        (field (name "MANUFACTURER") "Yageo")
        (field (name "MANUFACTURER PART NUMBER") "RC0805FR-0710KL")
      )
      (libsource (lib "28Pins_Project_V1I1") (part "RC0805FR-0710KL"))
    )
    (comp (ref "R22")
      (value "560R")
      (footprint "R0805")
      (description "RES SMD 560 OHM 1% 1/8W 0805")
      (fields
        (field (name "MANUFACTURER") "Yageo")
        (field (name "MANUFACTURER PART NUMBER") "RC0805FR-07560RL")
      )
      (libsource (lib "28Pins_Project_V1I1") (part "RC0805FR-07560RL"))
    )
    (comp (ref "R23")
      (value "22R")
      (footprint "R0805")
      (description "RES SMD 22 OHM 1% 1/8W 0805")
      (fields
        (field (name "MANUFACTURER") "Yageo")
        (field (name "MANUFACTURER PART NUMBER") "RC0805FR-0722RL")
      )
      (libsource (lib "28Pins_Project_V1I1") (part "RC0805FR-0722RL"))
    )
    (comp (ref "R24")
      (value "22R")
      (footprint "R0805")
      (description "RES SMD 22 OHM 1% 1/8W 0805")
      (fields
        (field (name "MANUFACTURER") "Yageo")
        (field (name "MANUFACTURER PART NUMBER") "RC0805FR-0722RL")
      )
      (libsource (lib "28Pins_Project_V1I1") (part "RC0805FR-0722RL"))
    )
    (comp (ref "R25")
      (value "22R")
      (footprint "R0805")
      (description "RES SMD 22 OHM 1% 1/8W 0805")
      (fields
        (field (name "MANUFACTURER") "Yageo")
        (field (name "MANUFACTURER PART NUMBER") "RC0805FR-0722RL")
      )
      (libsource (lib "28Pins_Project_V1I1") (part "RC0805FR-0722RL"))
    )
    (comp (ref "R26")
      (value "0R")
      (footprint "R0805")
      (description "YAGEO         RC0805JR-070RL             RES, THICK FILM, 0R, 0.125W, 0805")
      (fields
        (field (name "MANUFACTURER") "Yageo")
        (field (name "MANUFACTURER PART NUMBER") "RC0805JR-070RL")
      )
      (libsource (lib "28Pins_Project_V1I1") (part "RC0805JR-070RL"))
    )
    (comp (ref "R27")
      (value "0R")
      (footprint "R0805")
      (description "YAGEO         RC0805JR-070RL             RES, THICK FILM, 0R, 0.125W, 0805")
      (fields
        (field (name "MANUFACTURER") "Yageo")
        (field (name "MANUFACTURER PART NUMBER") "RC0805JR-070RL")
      )
      (libsource (lib "28Pins_Project_V1I1") (part "RC0805JR-070RL"))
    )
    (comp (ref "R28")
      (value "0R")
      (footprint "R0805")
      (description "YAGEO         RC0805JR-070RL             RES, THICK FILM, 0R, 0.125W, 0805")
      (fields
        (field (name "MANUFACTURER") "Yageo")
        (field (name "MANUFACTURER PART NUMBER") "RC0805JR-070RL")
      )
      (libsource (lib "28Pins_Project_V1I1") (part "RC0805JR-070RL"))
    )
    (comp (ref "SCKT FOR U1")
      (value "28-DIP Socket")
      (footprint "28_DIP_7.62mm_SOCKET")
      (description "SOCKET IC OPEN FRAME 28POS .3\"")
      (fields (field (name "MANUFACTURER") "3M") (field (name "MANUFACTURER PART NUMBER") "4828-3004-CP"))
      (libsource (lib "28Pins_Project_V1I1") (part "4828-3004-CP"))
    )
    (comp (ref "SW1")
      (value "1825910-6")
      (footprint "1825910-6")
      (description "Switch Push Button OFF (ON) SPST Round Button 0.05A 24VDC Momentary Contact PC Pins Thru-Hole")
      (fields (field (name "MANUFACTURER") "TE Connectivity Alcoswitch"))
      (libsource (lib "28Pins_Project_V1I1") (part "1825910-6"))
    )
    (comp (ref "SW2")
      (value "1825910-6")
      (footprint "1825910-6")
      (description "Switch Push Button OFF (ON) SPST Round Button 0.05A 24VDC Momentary Contact PC Pins Thru-Hole")
      (fields (field (name "MANUFACTURER") "TE Connectivity Alcoswitch"))
      (libsource (lib "28Pins_Project_V1I1") (part "1825910-6"))
    )
    (comp (ref "U1")
      (value "ATMEGA328P-PU")
      (footprint "28_DIP_7.62MM")
      (fields (field (name "MANUFACTURER") "Microchip / Atmel"))
      (libsource (lib "28Pins_Project_V1I1") (part "ATMEGA328P-PU"))
    )
    (comp (ref "U2")
      (value "ATMEGA16U2-AU")
      (footprint "TQFP32")
      (description "ATMEL         ATMEGA16U2-AU            MCU, 8BIT, MEGAAVR, 16MHZ, TQFP-32")
      (fields (field (name "MANUFACTURER") "Microchip / Atmel"))
      (libsource (lib "28Pins_Project_V1I1") (part "ATMEGA16U2-AU"))
    )
    (comp (ref "U3")
      (value "TL1963A-33DCQR")
      (footprint "DCQ (R-PDSO-G6)")
      (description "IC REG LDO 3.3V 1.5A SOT223-6")
      (fields (field (name "MANUFACTURER") "Texas Instruments"))
      (libsource (lib "28Pins_Project_V1I1") (part "TL1963A-33DCQR"))
    )
    (comp (ref "U4")
      (value "SN74AHC1G09DBVR")
      (footprint "DBV_SOT_23_5")
      (description "IC GATE AND 1CH 2-INP SOT-23-5")
      (fields (field (name "MANUFACTURER") "Texas Instruments"))
      (libsource (lib "28Pins_Project_V1I1") (part "SN74AHC1G09DBVR"))
    )
    (comp (ref "U5")
      (value "SN74AHC1G09DBVR")
      (footprint "DBV_SOT_23_5")
      (description "IC GATE AND 1CH 2-INP SOT-23-5")
      (fields (field (name "MANUFACTURER") "Texas Instruments"))
      (libsource (lib "28Pins_Project_V1I1") (part "SN74AHC1G09DBVR"))
    )
    (comp (ref "U6")
      (value "SN74AHC1G09DBVR")
      (footprint "DBV_SOT_23_5")
      (description "IC GATE AND 1CH 2-INP SOT-23-5")
      (fields (field (name "MANUFACTURER") "Texas Instruments"))
      (libsource (lib "28Pins_Project_V1I1") (part "SN74AHC1G09DBVR"))
    )
    (comp (ref "U7")
      (value "SN74AHC1G09DBVR")
      (footprint "DBV_SOT_23_5")
      (description "IC GATE AND 1CH 2-INP SOT-23-5")
      (fields (field (name "MANUFACTURER") "Texas Instruments"))
      (libsource (lib "28Pins_Project_V1I1") (part "SN74AHC1G09DBVR"))
    )
    (comp (ref "Y1")
      (value "ABM7-16.000MHZ-D2Y-T")
      (footprint "ABM7_v1_1_BIG")
      (description "Crystals 16.0MHz 20ppm 18pF -40C+85C")
      (fields (field (name "MANUFACTURER") "Abracon") (field (name "TOLERANCE") "20ppm"))
      (libsource (lib "28Pins_Project_V1I1") (part "ABM7-16.000MHZ-D2Y-T"))
    )
    (comp (ref "Y2")
      (value "ABM7-16.000MHZ-D2Y-T")
      (footprint "ABM7_v1_1_BIG")
      (description "Crystals 16.0MHz 20ppm 18pF -40C+85C")
      (fields (field (name "MANUFACTURER") "Abracon") (field (name "TOLERANCE") "20ppm"))
      (libsource (lib "28Pins_Project_V1I1") (part "ABM7-16.000MHZ-D2Y-T"))
    )
    (comp (ref "Z1")
      (value "CG0603MLC-05E")
      (footprint "R0603")
      (fields (field (name "MANUFACTURER") "Bourns") (field (name "VOLTAGE") "5V"))
      (libsource (lib "28Pins_Project_V1I1") (part "CG0603MLC-05E"))
    )
    (comp (ref "Z2")
      (value "CG0603MLC-05E")
      (footprint "R0603")
      (fields (field (name "MANUFACTURER") "Bourns") (field (name "VOLTAGE") "5V"))
      (libsource (lib "28Pins_Project_V1I1") (part "CG0603MLC-05E"))
    )
  )
  (nets
    (net (code "1") (name "+3V3") (class "Default")
      (node (ref "C13") (pin "2") (pinfunction "2_2") (pintype "passive"))
      (node (ref "C16") (pin "2") (pinfunction "2_2") (pintype "passive"))
      (node (ref "J1") (pin "4") (pinfunction "4_4") (pintype "passive"))
      (node (ref "JP4") (pin "3") (pinfunction "3_3") (pintype "passive"))
      (node (ref "R28") (pin "2") (pinfunction "2_2") (pintype "passive"))
      (node (ref "U3") (pin "4") (pinfunction "OUT_4") (pintype "passive"))
      (node (ref "U3") (pin "5") (pinfunction "SENSE_5") (pintype "passive"))
    )
    (net (code "2") (name "+5V") (class "Default")
      (node (ref "C12") (pin "2") (pinfunction "2_2") (pintype "passive"))
      (node (ref "C14") (pin "2") (pinfunction "2_2") (pintype "passive"))
      (node (ref "C2") (pin "1") (pinfunction "1_1") (pintype "passive"))
      (node (ref "C6") (pin "2") (pinfunction "2_2") (pintype "passive"))
      (node (ref "J1") (pin "5") (pinfunction "5_5") (pintype "passive"))
      (node (ref "J8") (pin "1") (pinfunction "1_1") (pintype "passive"))
      (node (ref "JP4") (pin "1") (pinfunction "1_1") (pintype "passive"))
      (node (ref "L1") (pin "2") (pinfunction "2_2") (pintype "passive"))
      (node (ref "R27") (pin "1") (pinfunction "1_1") (pintype "passive"))
      (node (ref "U2") (pin "31") (pinfunction "UVCC_31") (pintype "passive"))
      (node (ref "U3") (pin "1") (pinfunction "~{SHDN}_1") (pintype "passive"))
      (node (ref "U3") (pin "2") (pinfunction "IN_2") (pintype "passive"))
    )
    (net (code "3") (name "+5V{slash}3V3") (class "Default")
      (node (ref "C15") (pin "2") (pinfunction "2_2") (pintype "passive"))
      (node (ref "C17") (pin "2") (pinfunction "2_2") (pintype "passive"))
      (node (ref "C26") (pin "2") (pinfunction "2_2") (pintype "passive"))
      (node (ref "C28") (pin "2") (pinfunction "2_2") (pintype "passive"))
      (node (ref "C29") (pin "2") (pinfunction "2_2") (pintype "passive"))
      (node (ref "C30") (pin "2") (pinfunction "2_2") (pintype "passive"))
      (node (ref "C34") (pin "2") (pinfunction "2_2") (pintype "passive"))
      (node (ref "C8") (pin "2") (pinfunction "2_2") (pintype "passive"))
      (node (ref "D5") (pin "1") (pinfunction "Cathode_1") (pintype "passive"))
      (node (ref "D6") (pin "1") (pinfunction "Cathode_1") (pintype "passive"))
      (node (ref "FB1") (pin "1") (pinfunction "1_1") (pintype "passive"))
      (node (ref "FB2") (pin "1") (pinfunction "1_1") (pintype "passive"))
      (node (ref "FB3") (pin "1") (pinfunction "1_1") (pintype "passive"))
      (node (ref "J1") (pin "2") (pinfunction "2_2") (pintype "passive"))
      (node (ref "J5") (pin "2") (pinfunction "2_2") (pintype "passive"))
      (node (ref "J6") (pin "2") (pinfunction "2_2") (pintype "passive"))
      (node (ref "JP4") (pin "2") (pinfunction "2_2") (pintype "passive"))
      (node (ref "R1") (pin "2") (pinfunction "2_2") (pintype "passive"))
      (node (ref "R14") (pin "2") (pinfunction "2_2") (pintype "passive"))
      (node (ref "R15") (pin "2") (pinfunction "2_2") (pintype "passive"))
      (node (ref "R17") (pin "2") (pinfunction "2_2") (pintype "passive"))
      (node (ref "R18") (pin "2") (pinfunction "2_2") (pintype "passive"))
      (node (ref "R19") (pin "2") (pinfunction "2_2") (pintype "passive"))
      (node (ref "R2") (pin "2") (pinfunction "2_2") (pintype "passive"))
      (node (ref "R20") (pin "2") (pinfunction "2_2") (pintype "passive"))
      (node (ref "R21") (pin "2") (pinfunction "2_2") (pintype "passive"))
      (node (ref "R27") (pin "2") (pinfunction "2_2") (pintype "passive"))
      (node (ref "R28") (pin "1") (pinfunction "1_1") (pintype "passive"))
      (node (ref "R3") (pin "2") (pinfunction "2_2") (pintype "passive"))
      (node (ref "R4") (pin "2") (pinfunction "2_2") (pintype "passive"))
      (node (ref "U4") (pin "5") (pinfunction "5_5") (pintype "passive"))
      (node (ref "U5") (pin "5") (pinfunction "5_5") (pintype "passive"))
      (node (ref "U6") (pin "5") (pinfunction "5_5") (pintype "passive"))
      (node (ref "U7") (pin "5") (pinfunction "5_5") (pintype "passive"))
    )
    (net (code "4") (name "+AREF") (class "Default")
      (node (ref "C21") (pin "2") (pinfunction "2_2") (pintype "passive"))
      (node (ref "C24") (pin "2") (pinfunction "2_2") (pintype "passive"))
      (node (ref "J4") (pin "8") (pinfunction "8_8") (pintype "passive"))
      (node (ref "U1") (pin "21") (pinfunction "AREF_21") (pintype "passive"))
    )
    (net (code "5") (name "/+3V3_16U2_UCAP") (class "Default")
      (node (ref "C7") (pin "2") (pinfunction "2_2") (pintype "passive"))
      (node (ref "R26") (pin "1") (pinfunction "1_1") (pintype "passive"))
      (node (ref "U2") (pin "27") (pinfunction "UCAP_27") (pintype "passive"))
    )
    (net (code "6") (name "/+5V_USB") (class "Default")
      (node (ref "C1") (pin "1") (pinfunction "1_1") (pintype "passive"))
      (node (ref "J7") (pin "1") (pinfunction "1_1") (pintype "passive"))
      (node (ref "L1") (pin "1") (pinfunction "1_1") (pintype "passive"))
    )
    (net (code "7") (name "/+5V{slash}3V3_16U2") (class "Default")
      (node (ref "C3") (pin "2") (pinfunction "2_2") (pintype "passive"))
      (node (ref "C4") (pin "2") (pinfunction "2_2") (pintype "passive"))
      (node (ref "C5") (pin "2") (pinfunction "2_2") (pintype "passive"))
      (node (ref "FB1") (pin "2") (pinfunction "2_2") (pintype "passive"))
      (node (ref "R26") (pin "2") (pinfunction "2_2") (pintype "passive"))
      (node (ref "U2") (pin "32") (pinfunction "AVCC_32") (pintype "passive"))
      (node (ref "U2") (pin "4") (pinfunction "VCC_4") (pintype "passive"))
    )
    (net (code "8") (name "/+5V{slash}3V3_328P_AVCC") (class "Default")
      (node (ref "C22") (pin "2") (pinfunction "2_2") (pintype "passive"))
      (node (ref "C23") (pin "2") (pinfunction "2_2") (pintype "passive"))
      (node (ref "FB3") (pin "2") (pinfunction "2_2") (pintype "passive"))
      (node (ref "U1") (pin "20") (pinfunction "AVCC_20") (pintype "passive"))
    )
    (net (code "9") (name "/+5V{slash}3V3_328P_VCC") (class "Default")
      (node (ref "C19") (pin "2") (pinfunction "2_2") (pintype "passive"))
      (node (ref "C20") (pin "2") (pinfunction "2_2") (pintype "passive"))
      (node (ref "FB2") (pin "2") (pinfunction "2_2") (pintype "passive"))
      (node (ref "U1") (pin "7") (pinfunction "VCC_7") (pintype "passive"))
    )
    (net (code "10") (name "/16U2PROG_328P_RESETn") (class "Default")
      (node (ref "JP1") (pin "2") (pinfunction "2_2") (pintype "passive"))
      (node (ref "R1") (pin "1") (pinfunction "1_1") (pintype "passive"))
      (node (ref "U2") (pin "13") (pinfunction "~{CTS}_/~{_HWB}_/__T0_/_AIN6_/_INT7_/_PD7_13") (pintype "passive"))
    )
    (net (code "11") (name "/16U2_16MHZ_XTAL1") (class "Default")
      (node (ref "C10") (pin "2") (pinfunction "2_2") (pintype "passive"))
      (node (ref "R9") (pin "1") (pinfunction "1_1") (pintype "passive"))
      (node (ref "U2") (pin "1") (pinfunction "XTAL1_1") (pintype "passive"))
      (node (ref "Y2") (pin "1") (pinfunction "1_1") (pintype "passive"))
    )
    (net (code "12") (name "/16U2_16MHZ_XTAL2") (class "Default")
      (node (ref "C9") (pin "2") (pinfunction "2_2") (pintype "passive"))
      (node (ref "R9") (pin "2") (pinfunction "2_2") (pintype "passive"))
      (node (ref "U2") (pin "2") (pinfunction "XTAL2_/_PC0_2") (pintype "passive"))
      (node (ref "Y2") (pin "2") (pinfunction "2_2") (pintype "passive"))
    )
    (net (code "13") (name "/16U2_BUF_RESETn") (class "Default")
      (node (ref "C31") (pin "2") (pinfunction "2_2") (pintype "passive"))
      (node (ref "R23") (pin "2") (pinfunction "2_2") (pintype "passive"))
      (node (ref "U5") (pin "1") (pinfunction "1_1") (pintype "passive"))
      (node (ref "U5") (pin "2") (pinfunction "2_2") (pintype "passive"))
    )
    (net (code "14") (name "/16U2_HDR_RESETn") (class "Default")
      (node (ref "J6") (pin "5") (pinfunction "5_5") (pintype "passive"))
      (node (ref "JP3") (pin "3") (pinfunction "3_3") (pintype "passive"))
    )
    (net (code "15") (name "/16U2_MISO") (class "Default")
      (node (ref "J6") (pin "1") (pinfunction "1_1") (pintype "passive"))
      (node (ref "U2") (pin "17") (pinfunction "PDO_/_MISO_/_PCINT3_/_PB3_17") (pintype "passive"))
    )
    (net (code "16") (name "/16U2_MOSI") (class "Default")
      (node (ref "J6") (pin "4") (pinfunction "4_4") (pintype "passive"))
      (node (ref "U2") (pin "16") (pinfunction "PDI_/_MOSI_/_PCINT2_/_PB2_16") (pintype "passive"))
    )
    (net (code "17") (name "/16U2_PB4") (class "Default")
      (node (ref "JP2") (pin "1") (pinfunction "1_1") (pintype "passive"))
      (node (ref "JP3") (pin "2") (pinfunction "2_2") (pintype "passive"))
      (node (ref "U2") (pin "18") (pinfunction "T1_/_PCINT4_/_PB4_18") (pintype "passive"))
    )
    (net (code "18") (name "/16U2_PB5") (class "Default")
      (node (ref "JP2") (pin "3") (pinfunction "3_3") (pintype "passive"))
      (node (ref "U2") (pin "19") (pinfunction "PCINT5_/_PB5_19") (pintype "passive"))
    )
    (net (code "19") (name "/16U2_PB6") (class "Default")
      (node (ref "JP2") (pin "2") (pinfunction "2_2") (pintype "passive"))
      (node (ref "U2") (pin "20") (pinfunction "PCINT6_/_PB6_20") (pintype "passive"))
    )
    (net (code "20") (name "/16U2_PB7") (class "Default")
      (node (ref "JP2") (pin "4") (pinfunction "4_4") (pintype "passive"))
      (node (ref "U2") (pin "21") (pinfunction "OC.0A_/_OC.1C_/_PCINT7_/_PB7_21") (pintype "passive"))
    )
    (net (code "21") (name "/16U2_RESETn") (class "Default")
      (node (ref "JP3") (pin "4") (pinfunction "4_4") (pintype "passive"))
      (node (ref "R4") (pin "1") (pinfunction "1_1") (pintype "passive"))
      (node (ref "U2") (pin "24") (pinfunction "PC1_/~{_RESET}_/_DW_24") (pintype "passive"))
      (node (ref "U5") (pin "4") (pinfunction "4_4") (pintype "passive"))
    )
    (net (code "22") (name "/16U2_RXD") (class "Default")
      (node (ref "R11") (pin "1") (pinfunction "1_1") (pintype "passive"))
      (node (ref "U2") (pin "8") (pinfunction "RXD1_/_AIN1_/_INT2_/_PD2_8") (pintype "passive"))
    )
    (net (code "23") (name "/16U2_RX_LED") (class "Default")
      (node (ref "D4") (pin "1") (pinfunction "Cathode_1") (pintype "passive"))
      (node (ref "U2") (pin "10") (pinfunction "AIN3_/_INT5_/_PD4_10") (pintype "passive"))
    )
    (net (code "24") (name "/16U2_SCLK") (class "Default")
      (node (ref "J6") (pin "3") (pinfunction "3_3") (pintype "passive"))
      (node (ref "R5") (pin "2") (pinfunction "2_2") (pintype "passive"))
    )
    (net (code "25") (name "/16U2_SCLK_R") (class "Default")
      (node (ref "R5") (pin "1") (pinfunction "1_1") (pintype "passive"))
      (node (ref "U2") (pin "15") (pinfunction "SCLK_/_PCINT1_/_PB1_15") (pintype "passive"))
    )
    (net (code "26") (name "/16U2_TXD") (class "Default")
      (node (ref "R10") (pin "1") (pinfunction "1_1") (pintype "passive"))
      (node (ref "U2") (pin "9") (pinfunction "TXD1_/_INT3_/_PD3_9") (pintype "passive"))
    )
    (net (code "27") (name "/16U2_TX_LED") (class "Default")
      (node (ref "D3") (pin "1") (pinfunction "Cathode_1") (pintype "passive"))
      (node (ref "U2") (pin "11") (pinfunction "XCK_/_AIN4_/_PCINT12_/_PD5_11") (pintype "passive"))
    )
    (net (code "28") (name "/328P_16MHZ_XTAL1") (class "Default")
      (node (ref "C27") (pin "2") (pinfunction "2_2") (pintype "passive"))
      (node (ref "R16") (pin "1") (pinfunction "1_1") (pintype "passive"))
      (node (ref "U1") (pin "9") (pinfunction "PB6_/_PCINT6_/_TOSC1_/_XTAL1_9") (pintype "passive"))
      (node (ref "Y1") (pin "1") (pinfunction "1_1") (pintype "passive"))
    )
    (net (code "29") (name "/328P_16MHZ_XTAL2") (class "Default")
      (node (ref "C25") (pin "2") (pinfunction "2_2") (pintype "passive"))
      (node (ref "R16") (pin "2") (pinfunction "2_2") (pintype "passive"))
      (node (ref "U1") (pin "10") (pinfunction "PB7_/_PCINT7_/_TOSC2_/_XTAL2_10") (pintype "passive"))
      (node (ref "Y1") (pin "2") (pinfunction "2_2") (pintype "passive"))
    )
    (net (code "30") (name "/328P_AUTORESETn") (class "Default")
      (node (ref "C11") (pin "1") (pinfunction "1_1") (pintype "passive"))
      (node (ref "R18") (pin "1") (pinfunction "1_1") (pintype "passive"))
      (node (ref "U6") (pin "1") (pinfunction "1_1") (pintype "passive"))
    )
    (net (code "31") (name "/328P_BUF_RESETn") (class "Default")
      (node (ref "C32") (pin "2") (pinfunction "2_2") (pintype "passive"))
      (node (ref "R24") (pin "2") (pinfunction "2_2") (pintype "passive"))
      (node (ref "U6") (pin "2") (pinfunction "2_2") (pintype "passive"))
    )
    (net (code "32") (name "/328P_RESETn") (class "Default")
      (node (ref "J1") (pin "3") (pinfunction "3_3") (pintype "passive"))
      (node (ref "J5") (pin "5") (pinfunction "5_5") (pintype "passive"))
      (node (ref "JP3") (pin "1") (pinfunction "1_1") (pintype "passive"))
      (node (ref "R14") (pin "1") (pinfunction "1_1") (pintype "passive"))
      (node (ref "U1") (pin "1") (pinfunction "PC6_/_PCINT14_/_~{_RESET}_1") (pintype "passive"))
      (node (ref "U6") (pin "4") (pinfunction "4_4") (pintype "passive"))
    )
    (net (code "33") (name "/AD0") (class "Default")
      (node (ref "J2") (pin "1") (pinfunction "1_1") (pintype "passive"))
      (node (ref "U1") (pin "23") (pinfunction "PCINT8_/_ADC0_/_PC0_23") (pintype "passive"))
    )
    (net (code "34") (name "/AD1") (class "Default")
      (node (ref "J2") (pin "2") (pinfunction "2_2") (pintype "passive"))
      (node (ref "U1") (pin "24") (pinfunction "PCINT9_/_ADC1_/_PC1_24") (pintype "passive"))
    )
    (net (code "35") (name "/AD2") (class "Default")
      (node (ref "J2") (pin "3") (pinfunction "3_3") (pintype "passive"))
      (node (ref "U1") (pin "25") (pinfunction "PCINT10_/_ADC2_/_PC2_25") (pintype "passive"))
    )
    (net (code "36") (name "/AD3") (class "Default")
      (node (ref "J2") (pin "4") (pinfunction "4_4") (pintype "passive"))
      (node (ref "U1") (pin "26") (pinfunction "PCINT11_/_ADC3_/_PC3_26") (pintype "passive"))
    )
    (net (code "37") (name "/AD4{slash}SDA") (class "Default")
      (node (ref "J2") (pin "5") (pinfunction "5_5") (pintype "passive"))
      (node (ref "J4") (pin "9") (pinfunction "9_9") (pintype "passive"))
      (node (ref "U1") (pin "27") (pinfunction "SDA_/_PCINT12_/_ADC4_/_PC4_27") (pintype "passive"))
    )
    (net (code "38") (name "/AD5{slash}SCL") (class "Default")
      (node (ref "J2") (pin "6") (pinfunction "6_6") (pintype "passive"))
      (node (ref "J4") (pin "10") (pinfunction "10_10") (pintype "passive"))
      (node (ref "U1") (pin "28") (pinfunction "SCL_/_PCINT13_/_ADC5_/_PC5_28") (pintype "passive"))
    )
    (net (code "39") (name "/BUTTON_RESETn") (class "Default")
      (node (ref "D6") (pin "2") (pinfunction "Anode_2") (pintype "passive"))
      (node (ref "R20") (pin "1") (pinfunction "1_1") (pintype "passive"))
      (node (ref "R24") (pin "1") (pinfunction "1_1") (pintype "passive"))
      (node (ref "SW1") (pin "1") (pinfunction "1_1") (pintype "passive"))
      (node (ref "SW1") (pin "2") (pinfunction "2_2") (pintype "passive"))
    )
    (net (code "40") (name "/CON_USB_N") (class "Default")
      (node (ref "J7") (pin "2") (pinfunction "2_2") (pintype "passive"))
      (node (ref "R6") (pin "1") (pinfunction "1_1") (pintype "passive"))
      (node (ref "Z1") (pin "2") (pinfunction "2_2") (pintype "passive"))
    )
    (net (code "41") (name "/CON_USB_P") (class "Default")
      (node (ref "J7") (pin "3") (pinfunction "3_3") (pintype "passive"))
      (node (ref "R7") (pin "1") (pinfunction "1_1") (pintype "passive"))
      (node (ref "Z2") (pin "2") (pinfunction "2_2") (pintype "passive"))
    )
    (net (code "42") (name "/IO0") (class "Default")
      (node (ref "J3") (pin "1") (pinfunction "1_1") (pintype "passive"))
      (node (ref "R10") (pin "2") (pinfunction "2_2") (pintype "passive"))
      (node (ref "U1") (pin "2") (pinfunction "RXD_/_PCINT16_/_PD0_2") (pintype "passive"))
    )
    (net (code "43") (name "/IO1") (class "Default")
      (node (ref "J3") (pin "2") (pinfunction "2_2") (pintype "passive"))
      (node (ref "R11") (pin "2") (pinfunction "2_2") (pintype "passive"))
      (node (ref "U1") (pin "3") (pinfunction "TXD_/_PCINT17_/_PD1_3") (pintype "passive"))
    )
    (net (code "44") (name "/IO2") (class "Default")
      (node (ref "J3") (pin "3") (pinfunction "3_3") (pintype "passive"))
      (node (ref "U1") (pin "4") (pinfunction "INT0_/_PCINT18_/_PD2_4") (pintype "passive"))
    )
    (net (code "45") (name "/IO3") (class "Default")
      (node (ref "J3") (pin "4") (pinfunction "4_4") (pintype "passive"))
      (node (ref "U1") (pin "5") (pinfunction "OC2B_/_INT1_/_PCINT19_/_PD3_5") (pintype "passive"))
    )
    (net (code "46") (name "/IO4") (class "Default")
      (node (ref "J3") (pin "5") (pinfunction "5_5") (pintype "passive"))
      (node (ref "U1") (pin "6") (pinfunction "XCK_/_T0_/_PCINT20_/_PD4_6") (pintype "passive"))
    )
    (net (code "47") (name "/IO5") (class "Default")
      (node (ref "J3") (pin "6") (pinfunction "6_6") (pintype "passive"))
      (node (ref "U1") (pin "11") (pinfunction "OC0B_/_T1_/_PCINT21_/_PD5_11") (pintype "passive"))
    )
    (net (code "48") (name "/IO6") (class "Default")
      (node (ref "J3") (pin "7") (pinfunction "7_7") (pintype "passive"))
      (node (ref "U1") (pin "12") (pinfunction "OC0A_/_AIN0_/_PCINT22_/_PD6_12") (pintype "passive"))
    )
    (net (code "49") (name "/IO7") (class "Default")
      (node (ref "J3") (pin "8") (pinfunction "8_8") (pintype "passive"))
      (node (ref "U1") (pin "13") (pinfunction "AIN1_/_PCINT23_/_PD7_13") (pintype "passive"))
    )
    (net (code "50") (name "/IO8") (class "Default")
      (node (ref "J4") (pin "1") (pinfunction "1_1") (pintype "passive"))
      (node (ref "R22") (pin "2") (pinfunction "2_2") (pintype "passive"))
      (node (ref "U1") (pin "14") (pinfunction "CLKO_/_ICP1_/_PCINT0_/_PB0_14") (pintype "passive"))
    )
    (net (code "51") (name "/IO9") (class "Default")
      (node (ref "J4") (pin "2") (pinfunction "2_2") (pintype "passive"))
      (node (ref "U1") (pin "15") (pinfunction "OC1A_/_PCINT1_/_PB1_15") (pintype "passive"))
    )
    (net (code "52") (name "/MISO") (class "Default")
      (node (ref "J4") (pin "5") (pinfunction "5_5") (pintype "passive"))
      (node (ref "J5") (pin "1") (pinfunction "1_1") (pintype "passive"))
      (node (ref "U1") (pin "18") (pinfunction "MISO_/_PCINT4_/_PB4_18") (pintype "passive"))
    )
    (net (code "53") (name "/MOSI") (class "Default")
      (node (ref "J4") (pin "4") (pinfunction "4_4") (pintype "passive"))
      (node (ref "J5") (pin "4") (pinfunction "4_4") (pintype "passive"))
      (node (ref "U1") (pin "17") (pinfunction "MOSI_/_OC2A_/_PCINT3_/_PB3_17") (pintype "passive"))
    )
    (net (code "54") (name "/SCK") (class "Default")
      (node (ref "J4") (pin "6") (pinfunction "6_6") (pintype "passive"))
      (node (ref "J5") (pin "3") (pinfunction "3_3") (pintype "passive"))
      (node (ref "R13") (pin "2") (pinfunction "2_2") (pintype "passive"))
      (node (ref "U4") (pin "1") (pinfunction "1_1") (pintype "passive"))
      (node (ref "U4") (pin "2") (pinfunction "2_2") (pintype "passive"))
    )
    (net (code "55") (name "/SCK_R") (class "Default")
      (node (ref "R13") (pin "1") (pinfunction "1_1") (pintype "passive"))
      (node (ref "U1") (pin "19") (pinfunction "SCK_/_PCINT5_/_PB5_19") (pintype "passive"))
    )
    (net (code "56") (name "/SS") (class "Default")
      (node (ref "J4") (pin "3") (pinfunction "3_3") (pintype "passive"))
      (node (ref "U1") (pin "16") (pinfunction "~{SS}_/_OC1B_/_PCINT2_/_PB2_16") (pintype "passive"))
    )
    (net (code "57") (name "/USB_N") (class "Default")
      (node (ref "R6") (pin "2") (pinfunction "2_2") (pintype "passive"))
      (node (ref "U2") (pin "30") (pinfunction "D-_30") (pintype "passive"))
    )
    (net (code "58") (name "/USB_P") (class "Default")
      (node (ref "R7") (pin "2") (pinfunction "2_2") (pintype "passive"))
      (node (ref "U2") (pin "29") (pinfunction "D+_29") (pintype "passive"))
    )
    (net (code "59") (name "/USER_BUTTON") (class "Default")
      (node (ref "R21") (pin "1") (pinfunction "1_1") (pintype "passive"))
      (node (ref "R25") (pin "1") (pinfunction "1_1") (pintype "passive"))
      (node (ref "SW2") (pin "1") (pinfunction "1_1") (pintype "passive"))
      (node (ref "SW2") (pin "2") (pinfunction "2_2") (pintype "passive"))
    )
    (net (code "60") (name "/USER_BUTTON_BUF") (class "Default")
      (node (ref "C33") (pin "2") (pinfunction "2_2") (pintype "passive"))
      (node (ref "R25") (pin "2") (pinfunction "2_2") (pintype "passive"))
      (node (ref "U7") (pin "1") (pinfunction "1_1") (pintype "passive"))
      (node (ref "U7") (pin "2") (pinfunction "2_2") (pintype "passive"))
    )
    (net (code "61") (name "GND") (class "Default")
      (node (ref "C1") (pin "2") (pinfunction "2_2") (pintype "passive"))
      (node (ref "C10") (pin "1") (pinfunction "1_1") (pintype "passive"))
      (node (ref "C12") (pin "1") (pinfunction "1_1") (pintype "passive"))
      (node (ref "C13") (pin "1") (pinfunction "1_1") (pintype "passive"))
      (node (ref "C14") (pin "1") (pinfunction "1_1") (pintype "passive"))
      (node (ref "C15") (pin "1") (pinfunction "1_1") (pintype "passive"))
      (node (ref "C16") (pin "1") (pinfunction "1_1") (pintype "passive"))
      (node (ref "C17") (pin "1") (pinfunction "1_1") (pintype "passive"))
      (node (ref "C19") (pin "1") (pinfunction "1_1") (pintype "passive"))
      (node (ref "C2") (pin "2") (pinfunction "2_2") (pintype "passive"))
      (node (ref "C20") (pin "1") (pinfunction "1_1") (pintype "passive"))
      (node (ref "C21") (pin "1") (pinfunction "1_1") (pintype "passive"))
      (node (ref "C22") (pin "1") (pinfunction "1_1") (pintype "passive"))
      (node (ref "C23") (pin "1") (pinfunction "1_1") (pintype "passive"))
      (node (ref "C24") (pin "1") (pinfunction "1_1") (pintype "passive"))
      (node (ref "C25") (pin "1") (pinfunction "1_1") (pintype "passive"))
      (node (ref "C26") (pin "1") (pinfunction "1_1") (pintype "passive"))
      (node (ref "C27") (pin "1") (pinfunction "1_1") (pintype "passive"))
      (node (ref "C28") (pin "1") (pinfunction "1_1") (pintype "passive"))
      (node (ref "C29") (pin "1") (pinfunction "1_1") (pintype "passive"))
      (node (ref "C3") (pin "1") (pinfunction "1_1") (pintype "passive"))
      (node (ref "C30") (pin "1") (pinfunction "1_1") (pintype "passive"))
      (node (ref "C31") (pin "1") (pinfunction "1_1") (pintype "passive"))
      (node (ref "C32") (pin "1") (pinfunction "1_1") (pintype "passive"))
      (node (ref "C33") (pin "1") (pinfunction "1_1") (pintype "passive"))
      (node (ref "C34") (pin "1") (pinfunction "1_1") (pintype "passive"))
      (node (ref "C4") (pin "1") (pinfunction "1_1") (pintype "passive"))
      (node (ref "C5") (pin "1") (pinfunction "1_1") (pintype "passive"))
      (node (ref "C6") (pin "1") (pinfunction "1_1") (pintype "passive"))
      (node (ref "C7") (pin "1") (pinfunction "1_1") (pintype "passive"))
      (node (ref "C8") (pin "1") (pinfunction "1_1") (pintype "passive"))
      (node (ref "C9") (pin "1") (pinfunction "1_1") (pintype "passive"))
      (node (ref "D1") (pin "1") (pinfunction "Cathode_1") (pintype "passive"))
      (node (ref "J1") (pin "6") (pinfunction "6_6") (pintype "passive"))
      (node (ref "J1") (pin "7") (pinfunction "7_7") (pintype "passive"))
      (node (ref "J4") (pin "7") (pinfunction "7_7") (pintype "passive"))
      (node (ref "J5") (pin "6") (pinfunction "6_6") (pintype "passive"))
      (node (ref "J6") (pin "6") (pinfunction "6_6") (pintype "passive"))
      (node (ref "J7") (pin "10") (pinfunction "10_10") (pintype "passive"))
      (node (ref "J7") (pin "11") (pinfunction "11_11") (pintype "passive"))
      (node (ref "J7") (pin "5") (pinfunction "5_5") (pintype "passive"))
      (node (ref "J7") (pin "6") (pinfunction "6_6") (pintype "passive"))
      (node (ref "J7") (pin "7") (pinfunction "7_7") (pintype "passive"))
      (node (ref "J7") (pin "8") (pinfunction "8_8") (pintype "passive"))
      (node (ref "J7") (pin "9") (pinfunction "9_9") (pintype "passive"))
      (node (ref "J9") (pin "1") (pinfunction "1_1") (pintype "passive"))
      (node (ref "MH1") (pin "1") (pinfunction "1_1") (pintype "passive"))
      (node (ref "MH2") (pin "1") (pinfunction "1_1") (pintype "passive"))
      (node (ref "MH3") (pin "1") (pinfunction "1_1") (pintype "passive"))
      (node (ref "R12") (pin "1") (pinfunction "1_1") (pintype "passive"))
      (node (ref "R8") (pin "2") (pinfunction "2_2") (pintype "passive"))
      (node (ref "SW1") (pin "3") (pinfunction "3_3") (pintype "passive"))
      (node (ref "SW1") (pin "4") (pinfunction "4_4") (pintype "passive"))
      (node (ref "SW2") (pin "3") (pinfunction "3_3") (pintype "passive"))
      (node (ref "SW2") (pin "4") (pinfunction "4_4") (pintype "passive"))
      (node (ref "U1") (pin "22") (pinfunction "GND_2_22") (pintype "passive"))
      (node (ref "U1") (pin "8") (pinfunction "GND_1_8") (pintype "passive"))
      (node (ref "U2") (pin "28") (pinfunction "UGND_28") (pintype "passive"))
      (node (ref "U2") (pin "3") (pinfunction "GND_3") (pintype "passive"))
      (node (ref "U3") (pin "3") (pinfunction "GND_3") (pintype "passive"))
      (node (ref "U3") (pin "6") (pinfunction "EPAD_6") (pintype "passive"))
      (node (ref "U4") (pin "3") (pinfunction "3_3") (pintype "passive"))
      (node (ref "U5") (pin "3") (pinfunction "3_3") (pintype "passive"))
      (node (ref "U6") (pin "3") (pinfunction "3_3") (pintype "passive"))
      (node (ref "U7") (pin "3") (pinfunction "3_3") (pintype "passive"))
      (node (ref "Z1") (pin "1") (pinfunction "1_1") (pintype "passive"))
      (node (ref "Z2") (pin "1") (pinfunction "1_1") (pintype "passive"))
    )
    (net (code "62") (name "Net-(C11-Pad2)") (class "Default")
      (node (ref "C11") (pin "2") (pinfunction "2_2") (pintype "passive"))
      (node (ref "JP1") (pin "1") (pinfunction "1_1") (pintype "passive"))
    )
    (net (code "63") (name "Net-(D1-Anode)") (class "Default")
      (node (ref "D1") (pin "2") (pinfunction "Anode_2") (pintype "passive"))
      (node (ref "R17") (pin "1") (pinfunction "1_1") (pintype "passive"))
    )
    (net (code "64") (name "Net-(D2-Anode)") (class "Default")
      (node (ref "D2") (pin "2") (pinfunction "Anode_2") (pintype "passive"))
      (node (ref "R15") (pin "1") (pinfunction "1_1") (pintype "passive"))
    )
    (net (code "65") (name "Net-(D2-Cathode)") (class "Default")
      (node (ref "D2") (pin "1") (pinfunction "Cathode_1") (pintype "passive"))
      (node (ref "U4") (pin "4") (pinfunction "4_4") (pintype "passive"))
    )
    (net (code "66") (name "Net-(D3-Anode)") (class "Default")
      (node (ref "D3") (pin "2") (pinfunction "Anode_2") (pintype "passive"))
      (node (ref "R2") (pin "1") (pinfunction "1_1") (pintype "passive"))
    )
    (net (code "67") (name "Net-(D4-Anode)") (class "Default")
      (node (ref "D4") (pin "2") (pinfunction "Anode_2") (pintype "passive"))
      (node (ref "R3") (pin "1") (pinfunction "1_1") (pintype "passive"))
    )
    (net (code "68") (name "Net-(D5-Anode)") (class "Default")
      (node (ref "D5") (pin "2") (pinfunction "Anode_2") (pintype "passive"))
      (node (ref "R19") (pin "1") (pinfunction "1_1") (pintype "passive"))
      (node (ref "R23") (pin "1") (pinfunction "1_1") (pintype "passive"))
    )
    (net (code "69") (name "Net-(J7-Pad4)") (class "Default")
      (node (ref "J7") (pin "4") (pinfunction "4_4") (pintype "passive"))
      (node (ref "R8") (pin "1") (pinfunction "1_1") (pintype "passive"))
    )
    (net (code "70") (name "Net-(JP1-Pad3)") (class "Default")
      (node (ref "JP1") (pin "3") (pinfunction "3_3") (pintype "passive"))
      (node (ref "R12") (pin "2") (pinfunction "2_2") (pintype "passive"))
    )
    (net (code "71") (name "Net-(R22-Pad1)") (class "Default")
      (node (ref "R22") (pin "1") (pinfunction "1_1") (pintype "passive"))
      (node (ref "U7") (pin "4") (pinfunction "4_4") (pintype "passive"))
    )
    (net (code "72") (name "unconnected-(J1-Pad1)") (class "Default")
      (node (ref "J1") (pin "1") (pinfunction "1_1") (pintype "passive+no_connect"))
    )
    (net (code "73") (name "unconnected-(J1-Pad8)") (class "Default")
      (node (ref "J1") (pin "8") (pinfunction "8_8") (pintype "passive+no_connect"))
    )
    (net (code "74") (name "unconnected-(MH4-Pad1)") (class "Default")
      (node (ref "MH4") (pin "1") (pinfunction "1_1") (pintype "passive+no_connect"))
    )
    (net (code "75") (name "unconnected-(U2-AIN0_{slash}_INT1_{slash}_PD1-Pad7)") (class "Default")
      (node (ref "U2") (pin "7") (pinfunction "AIN0_/_INT1_/_PD1_7") (pintype "passive+no_connect"))
    )
    (net (code "76") (name "unconnected-(U2-AIN2_{slash}_PCINT11_{slash}_PC2-Pad5)") (class "Default")
      (node (ref "U2") (pin "5") (pinfunction "AIN2_/_PCINT11_/_PC2_5") (pintype "passive+no_connect"))
    )
    (net (code "77") (name "unconnected-(U2-CLKO_{slash}_ICP1_{slash}_INT4_{slash}_PC7-Pad22)") (class "Default")
      (node (ref "U2") (pin "22") (pinfunction "CLKO_/_ICP1_/_INT4_/_PC7_22") (pintype "passive+no_connect"))
    )
    (net (code "78") (name "unconnected-(U2-OC.0B_{slash}_INT0_{slash}_PD0-Pad6)") (class "Default")
      (node (ref "U2") (pin "6") (pinfunction "OC.0B_/_INT0_/_PD0_6") (pintype "passive+no_connect"))
    )
    (net (code "79") (name "unconnected-(U2-OC.1A_{slash}_PCINT8_{slash}_PC6-Pad23)") (class "Default")
      (node (ref "U2") (pin "23") (pinfunction "OC.1A_/_PCINT8_/_PC6_23") (pintype "passive+no_connect"))
    )
    (net (code "80") (name "unconnected-(U2-OC.1B_{slash}_PCINT9_{slash}_PC5-Pad25)") (class "Default")
      (node (ref "U2") (pin "25") (pinfunction "OC.1B_/_PCINT9_/_PC5_25") (pintype "passive+no_connect"))
    )
    (net (code "81") (name "unconnected-(U2-PCINT10_{slash}_PC4-Pad26)") (class "Default")
      (node (ref "U2") (pin "26") (pinfunction "PCINT10_/_PC4_26") (pintype "passive+no_connect"))
    )
    (net (code "82") (name "unconnected-(U2-~{RTS}_{slash}_AIN5_{slash}_INT6_{slash}_PD6-Pad12)") (class "Default")
      (node (ref "U2") (pin "12") (pinfunction "~{RTS}_/_AIN5_/_INT6_/_PD6_12") (pintype "passive+no_connect"))
    )
    (net (code "83") (name "unconnected-(U2-~{SS}_{slash}_PCINT0_{slash}_PB0-Pad14)") (class "Default")
      (node (ref "U2") (pin "14") (pinfunction "~{SS}_/_PCINT0_/_PB0_14") (pintype "passive+no_connect"))
    )
  )
)
